# V1_0.net
KiCad netlist of a schematic drawn in Altium Designer
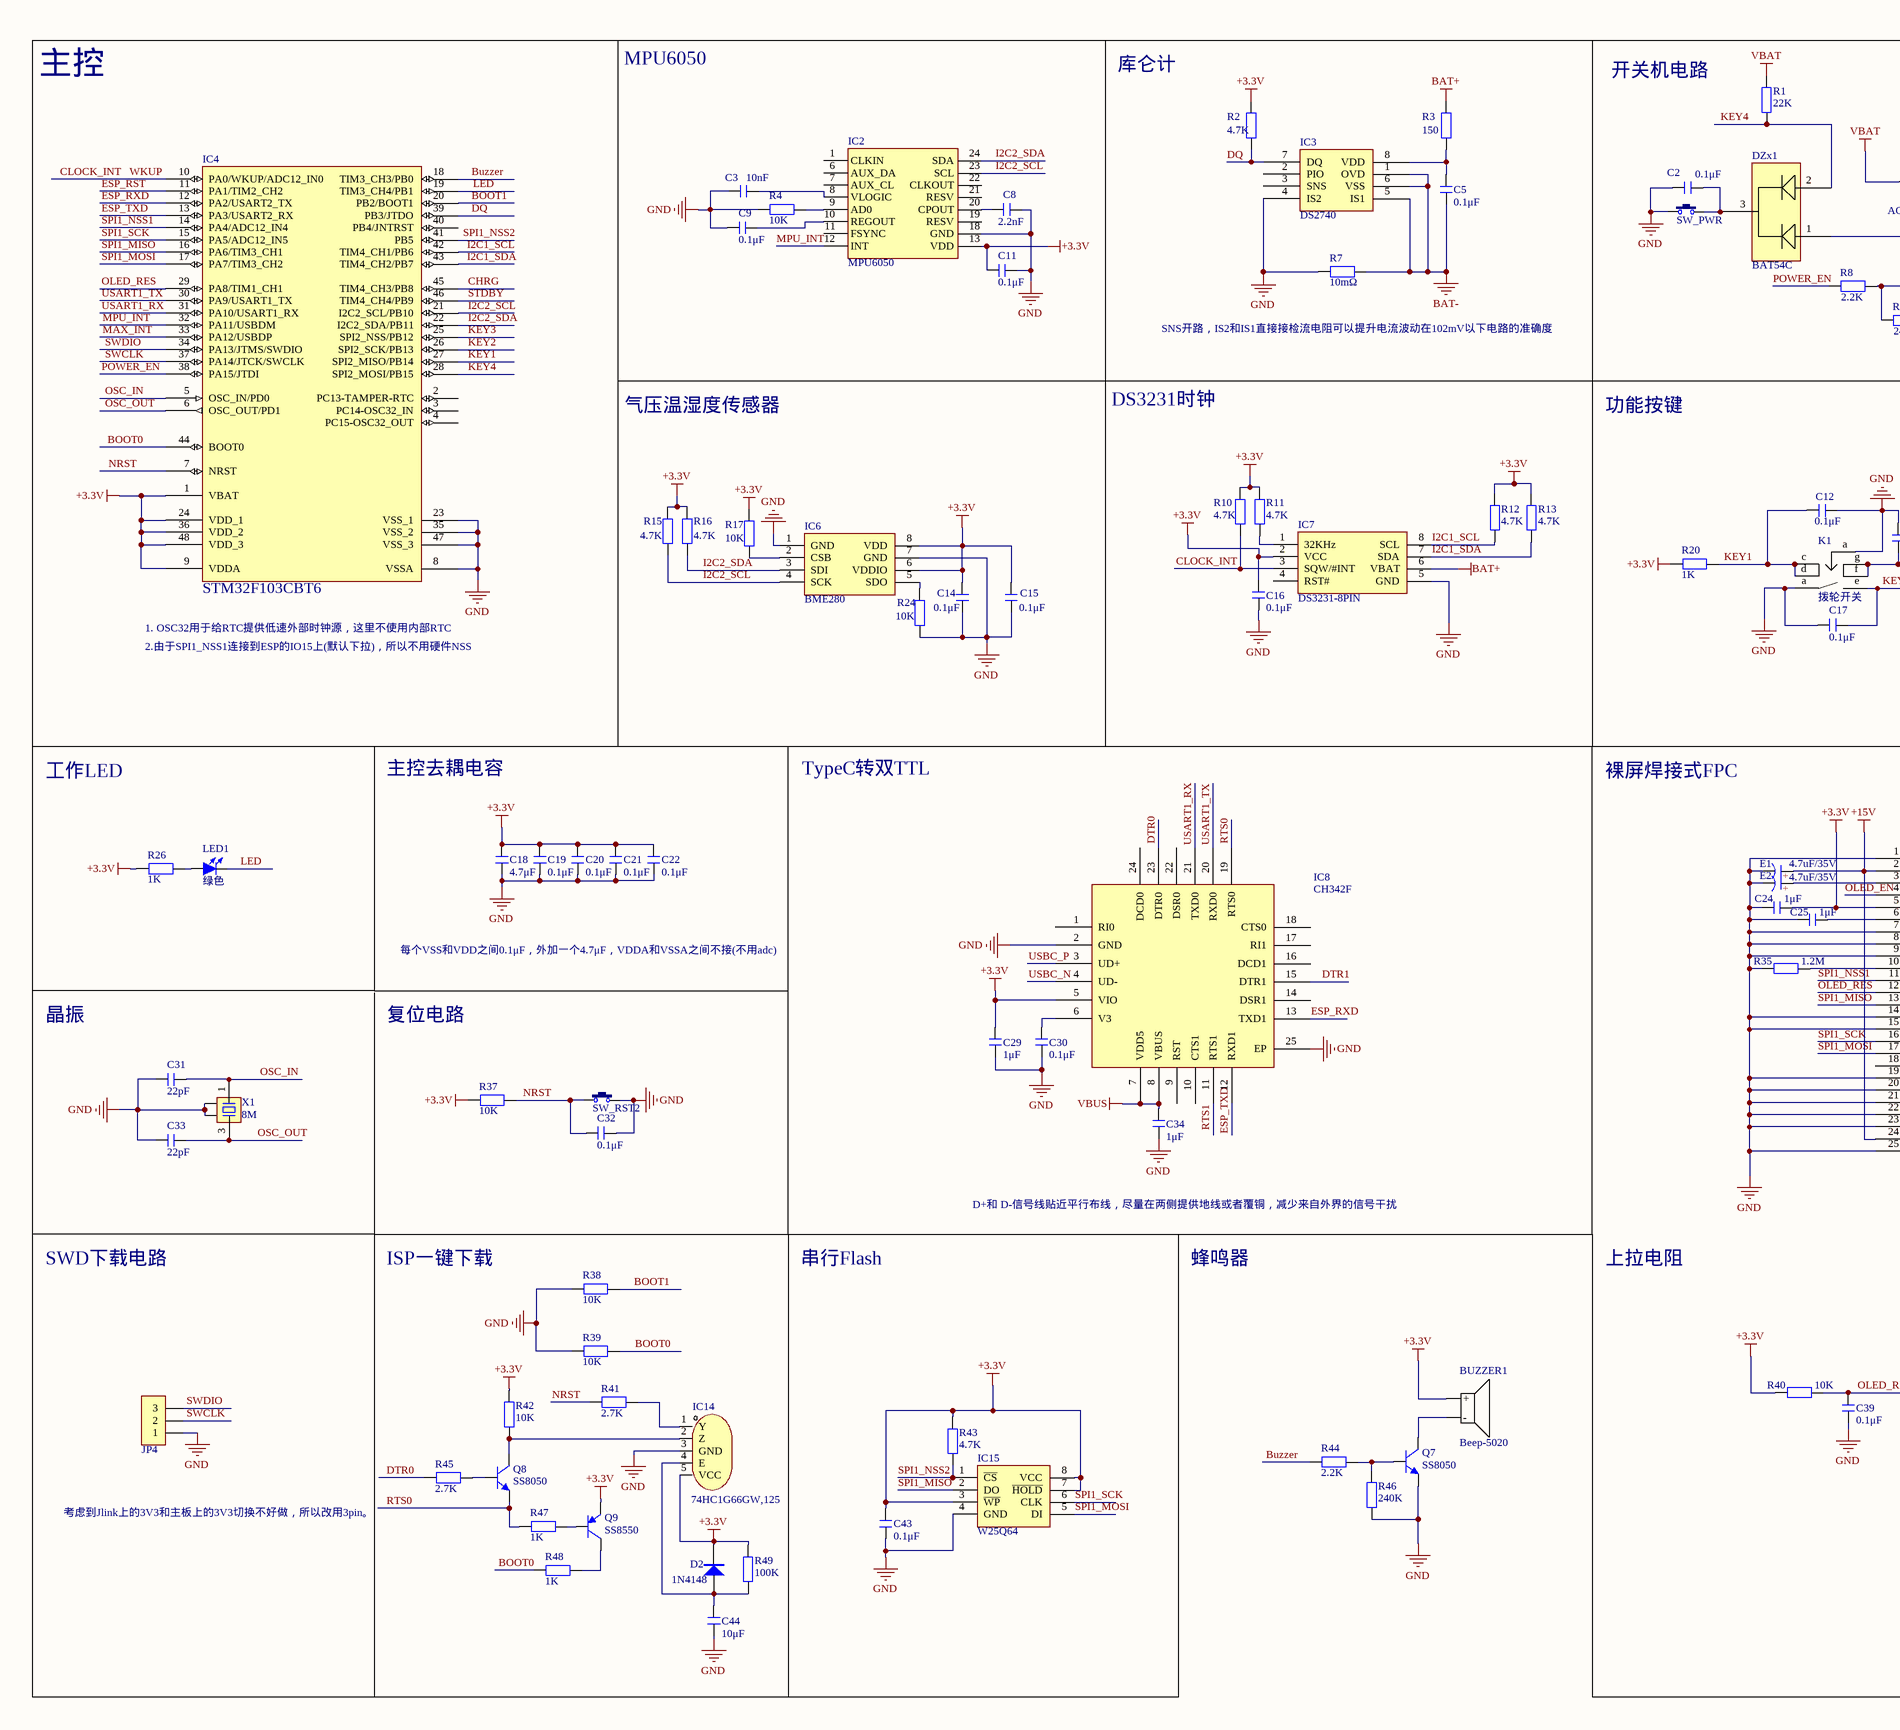
[diagram p0: V1.0.SchDoc, left]
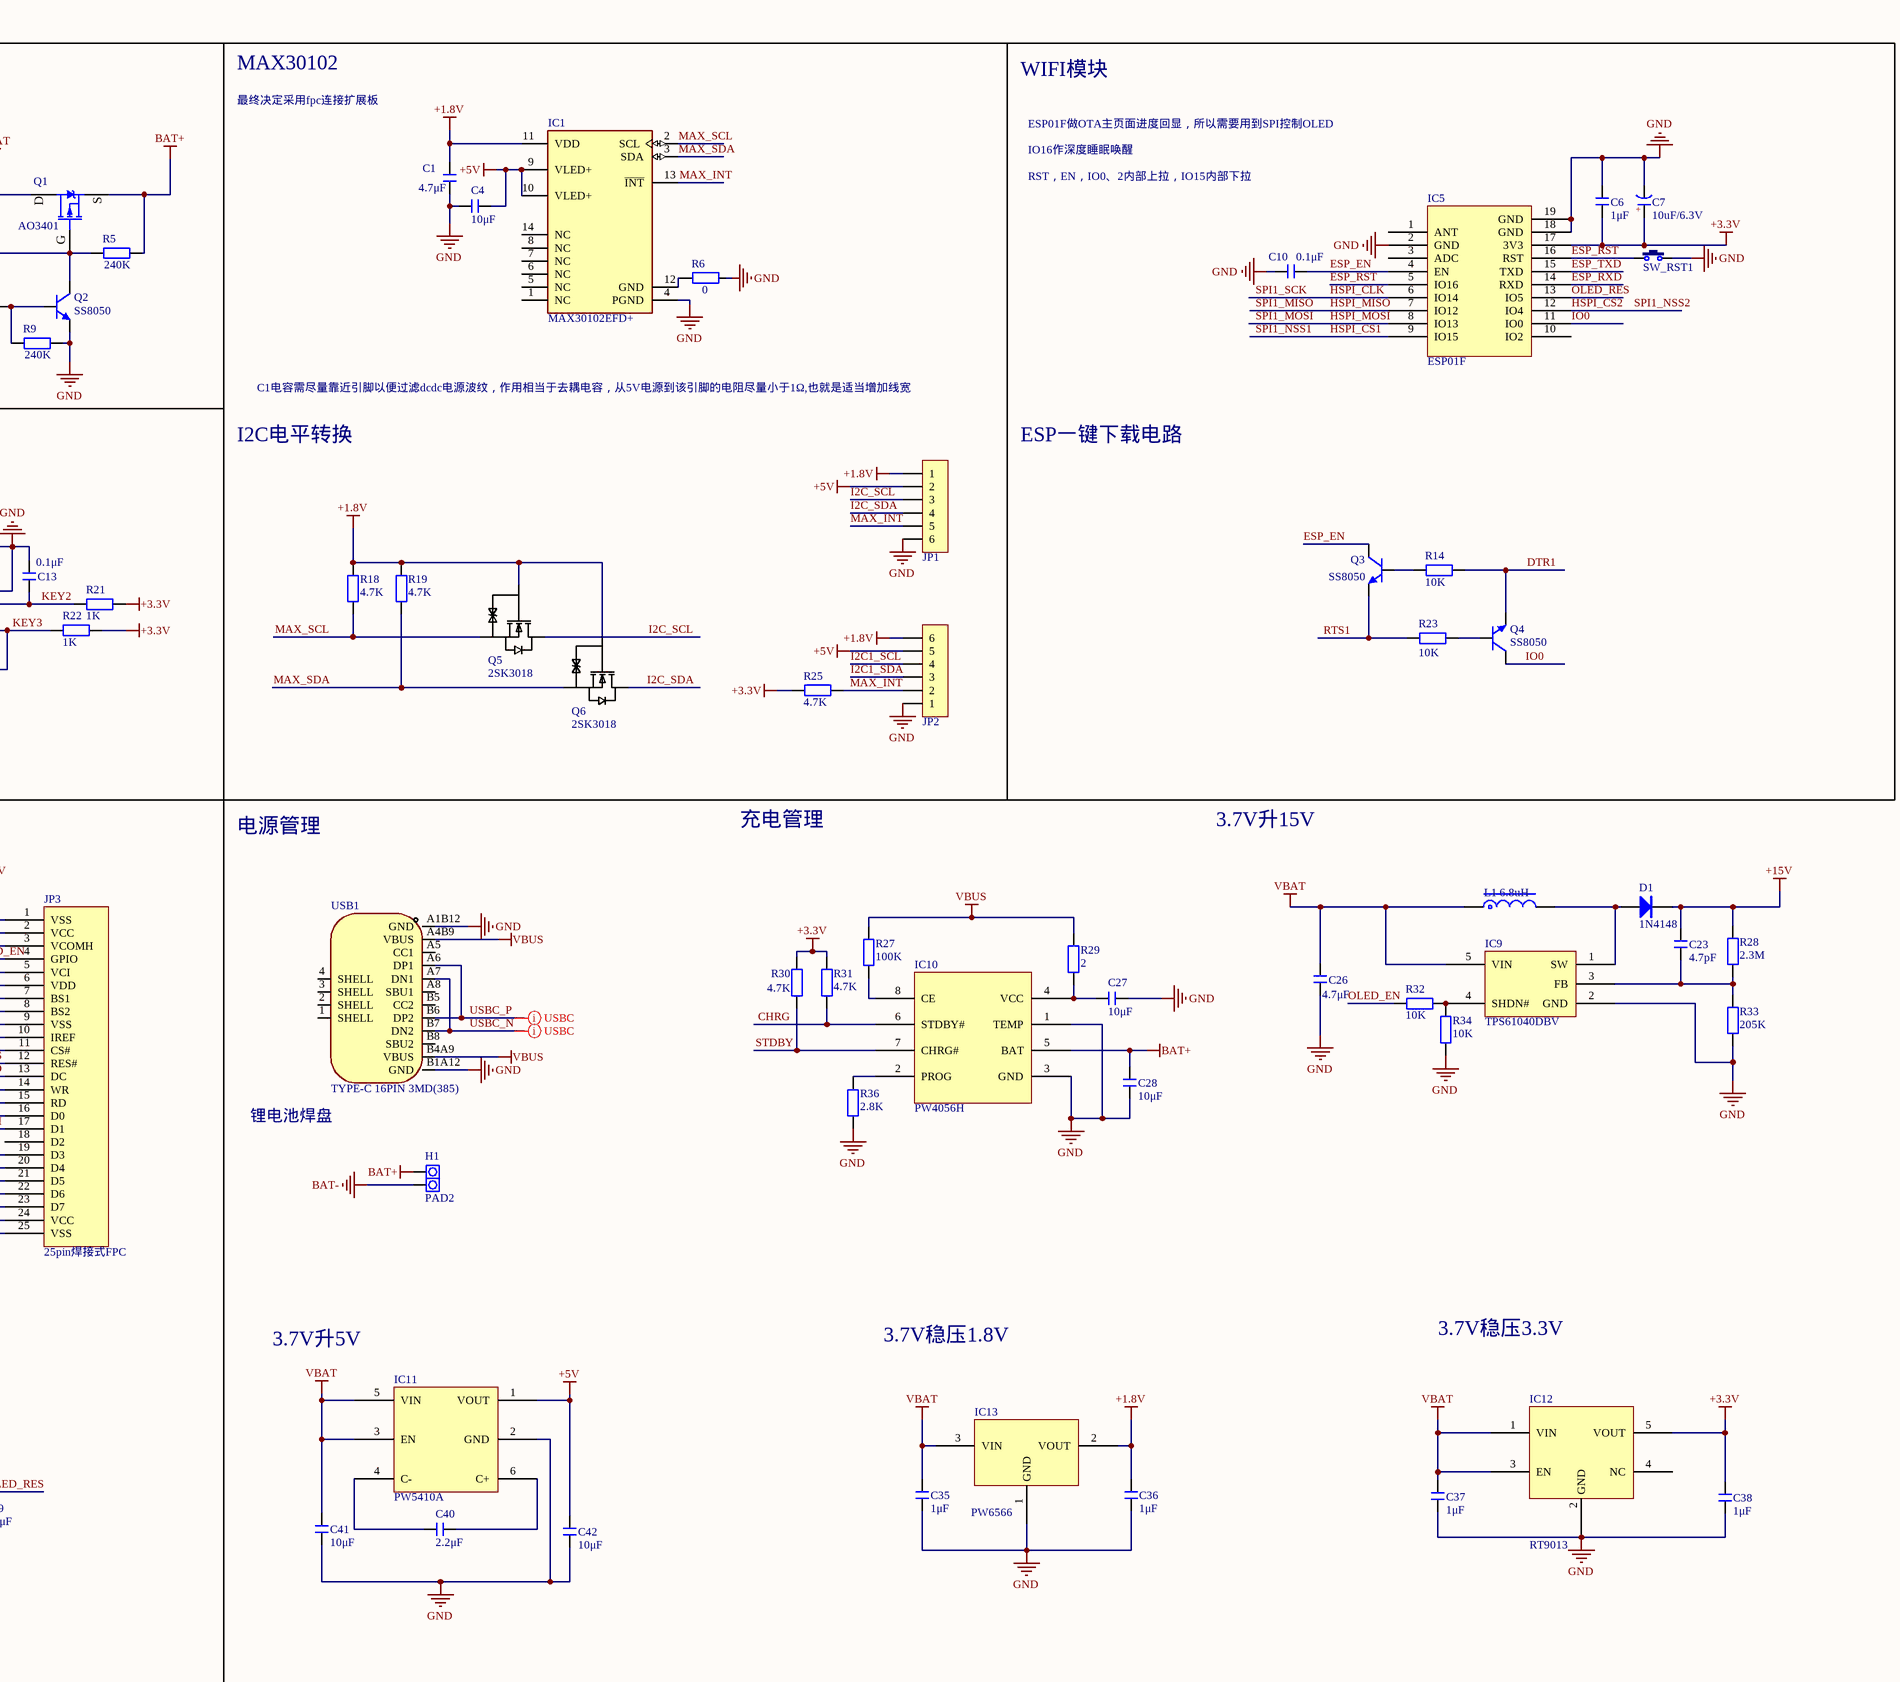
[diagram p1: V1.0.SchDoc, right]

(export (version "E")
  (design (tool "Eeschema 10.0.6"))
  (components
    (comp (ref "BUZZER1")
      (value "Beep-5020")
      (footprint "5020BUZZER")
      (description "贴片蜂鸣器5020最小封装")
      (libsource (lib "STM32_Watch") (part "Beep-5020"))
    )
    (comp (ref "C1")
      (value "4.7μF")
      (footprint "C 0603_L")
      (description "无极性贴片电容")
      (fields (field (name "版权归属") "源创客"))
      (libsource (lib "STM32_Watch") (part "C"))
    )
    (comp (ref "C2")
      (value "0.1μF")
      (footprint "C 0603_L")
      (description "无极性贴片电容")
      (fields (field (name "版权归属") "源创客"))
      (libsource (lib "STM32_Watch") (part "C"))
    )
    (comp (ref "C3")
      (value "10nF")
      (footprint "C 0603_L")
      (description "无极性贴片电容")
      (fields (field (name "版权归属") "源创客"))
      (libsource (lib "STM32_Watch") (part "C"))
    )
    (comp (ref "C4")
      (value "10μF")
      (footprint "C 0603_L")
      (description "无极性贴片电容")
      (fields (field (name "版权归属") "源创客"))
      (libsource (lib "STM32_Watch") (part "C"))
    )
    (comp (ref "C5")
      (value "0.1μF")
      (footprint "C 0603_L")
      (description "无极性贴片电容")
      (fields (field (name "版权归属") "源创客"))
      (libsource (lib "STM32_Watch") (part "C"))
    )
    (comp (ref "C6")
      (value "1μF")
      (footprint "C 0603_L")
      (description "无极性贴片电容")
      (fields (field (name "版权归属") "源创客"))
      (libsource (lib "STM32_Watch") (part "C"))
    )
    (comp (ref "C7")
      (value "10uF/6.3V")
      (footprint "CD A(3216)")
      (description "贴片钽电容")
      (fields (field (name "版权归属") "源创客"))
      (libsource (lib "STM32_Watch") (part "C-CD"))
    )
    (comp (ref "C8")
      (value "2.2nF")
      (footprint "C 0603_L")
      (description "无极性贴片电容")
      (fields (field (name "版权归属") "源创客"))
      (libsource (lib "STM32_Watch") (part "C"))
    )
    (comp (ref "C9")
      (value "0.1μF")
      (footprint "C 0603_L")
      (description "无极性贴片电容")
      (fields (field (name "版权归属") "源创客"))
      (libsource (lib "STM32_Watch") (part "C"))
    )
    (comp (ref "C10")
      (value "0.1μF")
      (footprint "C 0603_L")
      (description "无极性贴片电容")
      (fields (field (name "版权归属") "源创客"))
      (libsource (lib "STM32_Watch") (part "C"))
    )
    (comp (ref "C11")
      (value "0.1μF")
      (footprint "C 0603_L")
      (description "无极性贴片电容")
      (fields (field (name "版权归属") "源创客"))
      (libsource (lib "STM32_Watch") (part "C"))
    )
    (comp (ref "C12")
      (value "0.1μF")
      (footprint "C 0603_L")
      (description "无极性贴片电容")
      (fields (field (name "版权归属") "源创客"))
      (libsource (lib "STM32_Watch") (part "C"))
    )
    (comp (ref "C13")
      (value "0.1μF")
      (footprint "C 0603_L")
      (description "无极性贴片电容")
      (fields (field (name "版权归属") "源创客"))
      (libsource (lib "STM32_Watch") (part "C"))
    )
    (comp (ref "C14")
      (value "0.1μF")
      (footprint "C 0603_L")
      (description "无极性贴片电容")
      (fields (field (name "版权归属") "源创客"))
      (libsource (lib "STM32_Watch") (part "C"))
    )
    (comp (ref "C15")
      (value "0.1μF")
      (footprint "C 0603_L")
      (description "无极性贴片电容")
      (fields (field (name "版权归属") "源创客"))
      (libsource (lib "STM32_Watch") (part "C"))
    )
    (comp (ref "C16")
      (value "0.1μF")
      (footprint "C 0603_L")
      (description "无极性贴片电容")
      (fields (field (name "版权归属") "源创客"))
      (libsource (lib "STM32_Watch") (part "C"))
    )
    (comp (ref "C17")
      (value "0.1μF")
      (footprint "C 0603_L")
      (description "无极性贴片电容")
      (fields (field (name "版权归属") "源创客"))
      (libsource (lib "STM32_Watch") (part "C"))
    )
    (comp (ref "C18")
      (value "4.7μF")
      (footprint "C 0603_L")
      (description "无极性贴片电容")
      (fields (field (name "版权归属") "源创客"))
      (libsource (lib "STM32_Watch") (part "C"))
    )
    (comp (ref "C19")
      (value "0.1μF")
      (footprint "C 0603_L")
      (description "无极性贴片电容")
      (fields (field (name "版权归属") "源创客"))
      (libsource (lib "STM32_Watch") (part "C"))
    )
    (comp (ref "C20")
      (value "0.1μF")
      (footprint "C 0603_L")
      (description "无极性贴片电容")
      (fields (field (name "版权归属") "源创客"))
      (libsource (lib "STM32_Watch") (part "C"))
    )
    (comp (ref "C21")
      (value "0.1μF")
      (footprint "C 0603_L")
      (description "无极性贴片电容")
      (fields (field (name "版权归属") "源创客"))
      (libsource (lib "STM32_Watch") (part "C"))
    )
    (comp (ref "C22")
      (value "0.1μF")
      (footprint "C 0603_L")
      (description "无极性贴片电容")
      (fields (field (name "版权归属") "源创客"))
      (libsource (lib "STM32_Watch") (part "C"))
    )
    (comp (ref "C23")
      (value "4.7pF")
      (footprint "C 0603_L")
      (description "无极性贴片电容")
      (fields (field (name "版权归属") "源创客"))
      (libsource (lib "STM32_Watch") (part "C"))
    )
    (comp (ref "C24")
      (value "1μF")
      (footprint "C 0603_L")
      (description "无极性贴片电容")
      (fields (field (name "版权归属") "源创客"))
      (libsource (lib "STM32_Watch") (part "C"))
    )
    (comp (ref "C25")
      (value "1μF")
      (footprint "C 0603_L")
      (description "无极性贴片电容")
      (fields (field (name "版权归属") "源创客"))
      (libsource (lib "STM32_Watch") (part "C"))
    )
    (comp (ref "C26")
      (value "4.7μF")
      (footprint "C 0603_L")
      (description "无极性贴片电容")
      (fields (field (name "版权归属") "源创客"))
      (libsource (lib "STM32_Watch") (part "C"))
    )
    (comp (ref "C27")
      (value "10μF")
      (footprint "C 0603_L")
      (description "无极性贴片电容")
      (fields (field (name "版权归属") "源创客"))
      (libsource (lib "STM32_Watch") (part "C"))
    )
    (comp (ref "C28")
      (value "10μF")
      (footprint "C 0603_L")
      (description "无极性贴片电容")
      (fields (field (name "版权归属") "源创客"))
      (libsource (lib "STM32_Watch") (part "C"))
    )
    (comp (ref "C29")
      (value "1μF")
      (footprint "C 0603_L")
      (description "无极性贴片电容")
      (fields (field (name "版权归属") "源创客"))
      (libsource (lib "STM32_Watch") (part "C"))
    )
    (comp (ref "C30")
      (value "0.1μF")
      (footprint "C 0603_L")
      (description "无极性贴片电容")
      (fields (field (name "版权归属") "源创客"))
      (libsource (lib "STM32_Watch") (part "C"))
    )
    (comp (ref "C31")
      (value "22pF")
      (footprint "C 0603_L")
      (description "无极性贴片电容")
      (fields (field (name "版权归属") "源创客"))
      (libsource (lib "STM32_Watch") (part "C"))
    )
    (comp (ref "C32")
      (value "0.1μF")
      (footprint "C 0603_L")
      (description "无极性贴片电容")
      (fields (field (name "版权归属") "源创客"))
      (libsource (lib "STM32_Watch") (part "C"))
    )
    (comp (ref "C33")
      (value "22pF")
      (footprint "C 0603_L")
      (description "无极性贴片电容")
      (fields (field (name "版权归属") "源创客"))
      (libsource (lib "STM32_Watch") (part "C"))
    )
    (comp (ref "C34")
      (value "1μF")
      (footprint "C 0603_L")
      (description "无极性贴片电容")
      (fields (field (name "版权归属") "源创客"))
      (libsource (lib "STM32_Watch") (part "C"))
    )
    (comp (ref "C35")
      (value "1μF")
      (footprint "C 0603_L")
      (description "无极性贴片电容")
      (fields (field (name "版权归属") "源创客"))
      (libsource (lib "STM32_Watch") (part "C"))
    )
    (comp (ref "C36")
      (value "1μF")
      (footprint "C 0603_L")
      (description "无极性贴片电容")
      (fields (field (name "版权归属") "源创客"))
      (libsource (lib "STM32_Watch") (part "C"))
    )
    (comp (ref "C37")
      (value "1μF")
      (footprint "C 0603_L")
      (description "无极性贴片电容")
      (fields (field (name "版权归属") "源创客"))
      (libsource (lib "STM32_Watch") (part "C"))
    )
    (comp (ref "C38")
      (value "1μF")
      (footprint "C 0603_L")
      (description "无极性贴片电容")
      (fields (field (name "版权归属") "源创客"))
      (libsource (lib "STM32_Watch") (part "C"))
    )
    (comp (ref "C39")
      (value "0.1μF")
      (footprint "C 0603_L")
      (description "无极性贴片电容")
      (fields (field (name "版权归属") "源创客"))
      (libsource (lib "STM32_Watch") (part "C"))
    )
    (comp (ref "C40")
      (value "2.2μF")
      (footprint "C 0603_L")
      (description "无极性贴片电容")
      (fields (field (name "版权归属") "源创客"))
      (libsource (lib "STM32_Watch") (part "C"))
    )
    (comp (ref "C41")
      (value "10μF")
      (footprint "C 0603_L")
      (description "无极性贴片电容")
      (fields (field (name "版权归属") "源创客"))
      (libsource (lib "STM32_Watch") (part "C"))
    )
    (comp (ref "C42")
      (value "10μF")
      (footprint "C 0603_L")
      (description "无极性贴片电容")
      (fields (field (name "版权归属") "源创客"))
      (libsource (lib "STM32_Watch") (part "C"))
    )
    (comp (ref "C43")
      (value "0.1μF")
      (footprint "C 0603_L")
      (description "无极性贴片电容")
      (fields (field (name "版权归属") "源创客"))
      (libsource (lib "STM32_Watch") (part "C"))
    )
    (comp (ref "C44")
      (value "10μF")
      (footprint "C 0603_L")
      (description "无极性贴片电容")
      (fields (field (name "版权归属") "源创客"))
      (libsource (lib "STM32_Watch") (part "C"))
    )
    (comp (ref "D1")
      (value "1N4148")
      (footprint "SOD-123")
      (description "高速开关二极管")
      (fields (field (name "版权归属") "源创客"))
      (libsource (lib "STM32_Watch") (part "1N4148"))
    )
    (comp (ref "D2")
      (value "1N4148")
      (footprint "SOD-323")
      (description "高速开关二极管")
      (fields (field (name "版权归属") "源创客"))
      (libsource (lib "STM32_Watch") (part "1N4148"))
    )
    (comp (ref "DZx1")
      (value "BAT54C")
      (footprint "SOT23-3N")
      (description "双肖特基，共阴极")
      (libsource (lib "STM32_Watch") (part "BAT54C"))
    )
    (comp (ref "E1")
      (value "4.7uF/35V")
      (footprint "CD A(3216)")
      (description "贴片钽电容")
      (fields (field (name "版权归属") "源创客"))
      (libsource (lib "3.1   - 电阻-电容-电感") (part "C-CD"))
    )
    (comp (ref "E2")
      (value "4.7uF/35V")
      (footprint "CD A(3216)")
      (description "贴片钽电容")
      (fields (field (name "版权归属") "源创客"))
      (libsource (lib "3.1   - 电阻-电容-电感") (part "C-CD"))
    )
    (comp (ref "H1")
      (value "PAD2")
      (footprint "CHARGE_PAD")
      (description "引线焊盘")
      (fields (field (name "版权归属") "源创客"))
      (libsource (lib "STM32_Watch") (part "PAD2"))
    )
    (comp (ref "IC1")
      (value "MAX30102EFD+")
      (footprint "FP-F143A5-1-MFG")
      (description "IC SENSOR OXIMETER/HEARTRATE")
      (fields
        (field (name "MANUFACTURER") "Maxim Integrated")
        (field (name "OCTOPART") "https://octopart.com/max30102efd%2B-maxim+integrated-59568799")
      )
      (libsource (lib "STM32_Watch") (part "MAX30102"))
    )
    (comp (ref "IC2")
      (value "MPU6050")
      (footprint "QFN24 4x4_M")
      (description "陀螺仪")
      (libsource (lib "STM32_Watch") (part "MPU6050"))
    )
    (comp (ref "IC3")
      (value "DS2740")
      (footprint "MSOP8_L")
      (description "高精度库仑计")
      (libsource (lib "STM32_Watch") (part "DS2740"))
    )
    (comp (ref "IC4")
      (value "STM32F103CBT6")
      (footprint "LQFP48 7X7_M")
      (description "Flash:128/RAM:20/IO:48")
      (fields (field (name "版权归属") "源创客"))
      (libsource (lib "STM32_Watch") (part "STM32F103CB"))
    )
    (comp (ref "IC5") (value "ESP01F") (footprint "ESP-01F") (libsource (lib "STM32_Watch") (part "ESP01F")))
    (comp (ref "IC6")
      (value "BME280")
      (footprint "BME280")
      (description "气压，湿度，温度传感器")
      (libsource (lib "STM32_Watch") (part "BME280"))
    )
    (comp (ref "IC7")
      (value "DS3231-8PIN")
      (footprint "SOP8_N")
      (libsource (lib "STM32_Watch") (part "DS3231-8PIN"))
    )
    (comp (ref "IC8")
      (value "CH342F")
      (footprint "QFN24")
      (description "类型:-;协议类别:-;驱动器/接收器数:-;数据速率:-;")
      (fields (field (name "MANUFACTURER") "WCH(南京沁恒)"))
      (libsource (lib "STM32_Watch") (part "CH342F"))
    )
    (comp (ref "IC9")
      (value "TPS61040DBV")
      (footprint "SOT23-5L")
      (description "28V、400mA 开关升压转换器，适用于 LCD 和白光 LED")
      (libsource (lib "STM32_Watch") (part "TPS61040DBV"))
    )
    (comp (ref "IC10")
      (value "PW4056H")
      (footprint "SOP-8_L4.9-W3.9-P1.27-LS6.0-BL-EP3.1")
      (description "PW4056H 是一款完整的采用恒定电流/恒定电压的高压、大电流、单节鲤离子电池线性充电IC，最高耐压可达 28V，6.5V 自动过压保护，充电电流可达 1A。")
      (libsource (lib "STM32_Watch") (part "PW4056H"))
    )
    (comp (ref "IC11")
      (value "PW5410A")
      (footprint "SOT23-6")
      (description "低噪声，恒频 1.2MHZ，输入电压范围2.7v-5v，5v固定输出电压，输出电流250mA的DCDC升压")
      (libsource (lib "STM32_Watch") (part "PW5410A"))
    )
    (comp (ref "IC12")
      (value "RT9013")
      (footprint "SOT23-5L")
      (libsource (lib "STM32_Watch") (part "RT9013"))
    )
    (comp (ref "IC13")
      (value "PW6566")
      (footprint "SOT23-3L")
      (description "PW6566 系列是使用 CMOS 技术开发的低压差，高精度 输出电压，低消耗电流正电压型电压稳压器")
      (libsource (lib "STM32_Watch") (part "PW6566"))
    )
    (comp (ref "IC14")
      (value "74HC1G66GW,125")
      (footprint "SOT-353_L2.2-W1.4-P0.65-LS2.4-BR")
      (description "逻辑类型:SPST-NO;额外特性:-;")
      (fields (field (name "MANUFACTURER") "Nexperia(安世)"))
      (libsource (lib "STM32_Watch") (part "74HC1G66GW,125"))
    )
    (comp (ref "IC15")
      (value "W25Q64")
      (footprint "SOP8W_N")
      (description "外置Flash")
      (fields (field (name "版权归属") "源创客"))
      (libsource (lib "1.1   - IC芯片") (part "W25Qxx"))
    )
    (comp (ref "JP1")
      (value "FPC1.0-6P")
      (footprint "FPC0.5 2H-WS-6P")
      (description "FPC连接器")
      (fields (field (name "版权归属") "源创客"))
      (libsource (lib "") (part "FPC-6P_1"))
    )
    (comp (ref "JP2")
      (value "FPC1.0-6P")
      (footprint "FPC0.5 2H-WS-6P")
      (description "FPC连接器")
      (fields (field (name "版权归属") "源创客"))
      (libsource (lib "STM32_Watch") (part "FPC-6P"))
    )
    (comp (ref "JP3")
      (value "25pin焊接式FPC")
      (footprint "25pin焊接式FPC")
      (libsource (lib "STM32_Watch") (part "25pin焊接式FPC"))
    )
    (comp (ref "JP4")
      (value "HDR-1X3")
      (footprint "HDR2.54-3P")
      (description "3P接插件")
      (fields (field (name "版权归属") "源创客"))
      (libsource (lib "STM32_Watch") (part "Header 3"))
    )
    (comp (ref "K1") (value "拨轮开关") (footprint "拨轮开关") (libsource (lib "STM32_Watch") (part "拨轮开关")))
    (comp (ref "L1")
      (value "6.8uH")
      (footprint "NR3015")
      (description "NR磁胶电感")
      (fields (field (name "版权归属") "源创客"))
      (libsource (lib "STM32_Watch") (part "L-NR"))
    )
    (comp (ref "LED1")
      (value "绿色")
      (footprint "LED 0603G")
      (description "贴片LED")
      (fields (field (name "版权归属") "源创客"))
      (libsource (lib "STM32_Watch") (part "LED-SMD"))
    )
    (comp (ref "Q1")
      (value "AO3401")
      (footprint "SOT23-3N")
      (description "P沟道场效应管")
      (fields (field (name "版权归属") "源创客"))
      (libsource (lib "STM32_Watch") (part "AO3401"))
    )
    (comp (ref "Q2")
      (value "SS8050")
      (footprint "SOT23-3N")
      (description "高频放大-NPN型")
      (fields (field (name "版权归属") "源创客"))
      (libsource (lib "STM32_Watch") (part "8050-SMD"))
    )
    (comp (ref "Q3")
      (value "SS8050")
      (footprint "SOT23-3N")
      (description "高频放大-NPN型")
      (fields (field (name "版权归属") "源创客"))
      (libsource (lib "STM32_Watch") (part "8050-SMD"))
    )
    (comp (ref "Q4")
      (value "SS8050")
      (footprint "SOT23-3N")
      (description "高频放大-NPN型")
      (fields (field (name "版权归属") "源创客"))
      (libsource (lib "STM32_Watch") (part "8050-SMD"))
    )
    (comp (ref "Q5")
      (value "2SK3018")
      (footprint "SOT23-3L")
      (fields (field (name "MANUFACTURER") "TWGMC(台湾迪嘉)"))
      (libsource (lib "STM32_Watch") (part "2SK3018"))
    )
    (comp (ref "Q6")
      (value "2SK3018")
      (footprint "SOT23-3L")
      (fields (field (name "MANUFACTURER") "TWGMC(台湾迪嘉)"))
      (libsource (lib "STM32_Watch") (part "2SK3018"))
    )
    (comp (ref "Q7")
      (value "SS8050")
      (footprint "SOT23-3N")
      (description "高频放大-NPN型")
      (fields (field (name "版权归属") "源创客"))
      (libsource (lib "STM32_Watch") (part "8050-SMD"))
    )
    (comp (ref "Q8")
      (value "SS8050")
      (footprint "SOT23-3N")
      (description "高频放大-NPN型")
      (fields (field (name "版权归属") "源创客"))
      (libsource (lib "STM32_Watch") (part "8050-SMD"))
    )
    (comp (ref "Q9")
      (value "SS8550")
      (footprint "SOT23-3N")
      (description "高频放大-PNP型")
      (fields (field (name "版权归属") "源创客"))
      (libsource (lib "STM32_Watch") (part "8550-SMD"))
    )
    (comp (ref "R1")
      (value "22K")
      (footprint "R 0603_L")
      (description "贴片电阻")
      (fields (field (name "版权归属") "源创客"))
      (libsource (lib "STM32_Watch") (part "R"))
    )
    (comp (ref "R2")
      (value "4.7K")
      (footprint "R 0603_L")
      (description "贴片电阻")
      (fields (field (name "版权归属") "源创客"))
      (libsource (lib "STM32_Watch") (part "R"))
    )
    (comp (ref "R3")
      (value "150")
      (footprint "R 0603_L")
      (description "贴片电阻")
      (fields (field (name "版权归属") "源创客"))
      (libsource (lib "STM32_Watch") (part "R"))
    )
    (comp (ref "R4")
      (value "10K")
      (footprint "R 0603_L")
      (description "贴片电阻")
      (fields (field (name "版权归属") "源创客"))
      (libsource (lib "STM32_Watch") (part "R"))
    )
    (comp (ref "R5")
      (value "240K")
      (footprint "R 0603_L")
      (description "贴片电阻")
      (fields (field (name "版权归属") "源创客"))
      (libsource (lib "STM32_Watch") (part "R"))
    )
    (comp (ref "R6")
      (value "0")
      (footprint "R 0603_L")
      (description "贴片电阻")
      (fields (field (name "版权归属") "源创客"))
      (libsource (lib "STM32_Watch") (part "R"))
    )
    (comp (ref "R7")
      (value "10mΩ")
      (footprint "R 0603_L")
      (description "贴片电阻")
      (fields (field (name "版权归属") "源创客"))
      (libsource (lib "STM32_Watch") (part "R"))
    )
    (comp (ref "R8")
      (value "2.2K")
      (footprint "R 0603_L")
      (description "贴片电阻")
      (fields (field (name "版权归属") "源创客"))
      (libsource (lib "STM32_Watch") (part "R"))
    )
    (comp (ref "R9")
      (value "240K")
      (footprint "R 0603_L")
      (description "贴片电阻")
      (fields (field (name "版权归属") "源创客"))
      (libsource (lib "STM32_Watch") (part "R"))
    )
    (comp (ref "R10")
      (value "4.7K")
      (footprint "R 0603_L")
      (description "贴片电阻")
      (fields (field (name "版权归属") "源创客"))
      (libsource (lib "STM32_Watch") (part "R"))
    )
    (comp (ref "R11")
      (value "4.7K")
      (footprint "R 0603_L")
      (description "贴片电阻")
      (fields (field (name "版权归属") "源创客"))
      (libsource (lib "STM32_Watch") (part "R"))
    )
    (comp (ref "R12")
      (value "4.7K")
      (footprint "R 0603_L")
      (description "贴片电阻")
      (fields (field (name "版权归属") "源创客"))
      (libsource (lib "STM32_Watch") (part "R"))
    )
    (comp (ref "R13")
      (value "4.7K")
      (footprint "R 0603_L")
      (description "贴片电阻")
      (fields (field (name "版权归属") "源创客"))
      (libsource (lib "STM32_Watch") (part "R"))
    )
    (comp (ref "R14")
      (value "10K")
      (footprint "R 0603_L")
      (description "贴片电阻")
      (fields (field (name "版权归属") "源创客"))
      (libsource (lib "STM32_Watch") (part "R"))
    )
    (comp (ref "R15")
      (value "4.7K")
      (footprint "R 0603_L")
      (description "贴片电阻")
      (fields (field (name "版权归属") "源创客"))
      (libsource (lib "STM32_Watch") (part "R"))
    )
    (comp (ref "R16")
      (value "4.7K")
      (footprint "R 0603_L")
      (description "贴片电阻")
      (fields (field (name "版权归属") "源创客"))
      (libsource (lib "STM32_Watch") (part "R"))
    )
    (comp (ref "R17")
      (value "10K")
      (footprint "R 0603_L")
      (description "贴片电阻")
      (fields (field (name "版权归属") "源创客"))
      (libsource (lib "STM32_Watch") (part "R"))
    )
    (comp (ref "R18")
      (value "4.7K")
      (footprint "R 0603_L")
      (description "贴片电阻")
      (fields (field (name "版权归属") "源创客"))
      (libsource (lib "STM32_Watch") (part "R"))
    )
    (comp (ref "R19")
      (value "4.7K")
      (footprint "R 0603_L")
      (description "贴片电阻")
      (fields (field (name "版权归属") "源创客"))
      (libsource (lib "STM32_Watch") (part "R"))
    )
    (comp (ref "R20")
      (value "1K")
      (footprint "R 0603_L")
      (description "贴片电阻")
      (fields (field (name "版权归属") "源创客"))
      (libsource (lib "STM32_Watch") (part "R"))
    )
    (comp (ref "R21")
      (value "1K")
      (footprint "R 0603_L")
      (description "贴片电阻")
      (fields (field (name "版权归属") "源创客"))
      (libsource (lib "STM32_Watch") (part "R"))
    )
    (comp (ref "R22")
      (value "1K")
      (footprint "R 0603_L")
      (description "贴片电阻")
      (fields (field (name "版权归属") "源创客"))
      (libsource (lib "STM32_Watch") (part "R"))
    )
    (comp (ref "R23")
      (value "10K")
      (footprint "R 0603_L")
      (description "贴片电阻")
      (fields (field (name "版权归属") "源创客"))
      (libsource (lib "STM32_Watch") (part "R"))
    )
    (comp (ref "R24")
      (value "10K")
      (footprint "R 0603_L")
      (description "贴片电阻")
      (fields (field (name "版权归属") "源创客"))
      (libsource (lib "STM32_Watch") (part "R"))
    )
    (comp (ref "R25")
      (value "4.7K")
      (footprint "R 0603_L")
      (description "贴片电阻")
      (fields (field (name "版权归属") "源创客"))
      (libsource (lib "STM32_Watch") (part "R"))
    )
    (comp (ref "R26")
      (value "1K")
      (footprint "R 0603_L")
      (description "贴片电阻")
      (fields (field (name "版权归属") "源创客"))
      (libsource (lib "STM32_Watch") (part "R"))
    )
    (comp (ref "R27")
      (value "100K")
      (footprint "R 0603_L")
      (description "贴片电阻")
      (fields (field (name "版权归属") "源创客"))
      (libsource (lib "STM32_Watch") (part "R"))
    )
    (comp (ref "R28")
      (value "2.3M")
      (footprint "R 0603_L")
      (description "贴片电阻")
      (fields (field (name "版权归属") "源创客"))
      (libsource (lib "STM32_Watch") (part "R"))
    )
    (comp (ref "R29")
      (value "2")
      (footprint "R 0603_L")
      (description "贴片电阻")
      (fields (field (name "版权归属") "源创客"))
      (libsource (lib "STM32_Watch") (part "R"))
    )
    (comp (ref "R30")
      (value "4.7K")
      (footprint "R 0603_L")
      (description "贴片电阻")
      (fields (field (name "版权归属") "源创客"))
      (libsource (lib "STM32_Watch") (part "R"))
    )
    (comp (ref "R31")
      (value "4.7K")
      (footprint "R 0603_L")
      (description "贴片电阻")
      (fields (field (name "版权归属") "源创客"))
      (libsource (lib "STM32_Watch") (part "R"))
    )
    (comp (ref "R32")
      (value "10K")
      (footprint "R 0603_L")
      (description "贴片电阻")
      (fields (field (name "版权归属") "源创客"))
      (libsource (lib "STM32_Watch") (part "R"))
    )
    (comp (ref "R33")
      (value "205K")
      (footprint "R 0603_L")
      (description "贴片电阻")
      (fields (field (name "版权归属") "源创客"))
      (libsource (lib "STM32_Watch") (part "R"))
    )
    (comp (ref "R34")
      (value "10K")
      (footprint "R 0603_L")
      (description "贴片电阻")
      (fields (field (name "版权归属") "源创客"))
      (libsource (lib "STM32_Watch") (part "R"))
    )
    (comp (ref "R35")
      (value "1.2M")
      (footprint "R 0603_L")
      (description "贴片电阻")
      (fields (field (name "版权归属") "源创客"))
      (libsource (lib "STM32_Watch") (part "R"))
    )
    (comp (ref "R36")
      (value "2.8K")
      (footprint "R 0603_L")
      (description "贴片电阻")
      (fields (field (name "版权归属") "源创客"))
      (libsource (lib "STM32_Watch") (part "R"))
    )
    (comp (ref "R37")
      (value "10K")
      (footprint "R 0603_L")
      (description "贴片电阻")
      (fields (field (name "版权归属") "源创客"))
      (libsource (lib "STM32_Watch") (part "R"))
    )
    (comp (ref "R38")
      (value "10K")
      (footprint "R 0603_L")
      (description "贴片电阻")
      (fields (field (name "版权归属") "源创客"))
      (libsource (lib "STM32_Watch") (part "R"))
    )
    (comp (ref "R39")
      (value "10K")
      (footprint "R 0603_L")
      (description "贴片电阻")
      (fields (field (name "版权归属") "源创客"))
      (libsource (lib "STM32_Watch") (part "R"))
    )
    (comp (ref "R40")
      (value "10K")
      (footprint "R 0603_L")
      (description "贴片电阻")
      (fields (field (name "版权归属") "源创客"))
      (libsource (lib "STM32_Watch") (part "R"))
    )
    (comp (ref "R41")
      (value "2.7K")
      (footprint "R 0603_L")
      (description "贴片电阻")
      (fields (field (name "版权归属") "源创客"))
      (libsource (lib "STM32_Watch") (part "R"))
    )
    (comp (ref "R42")
      (value "10K")
      (footprint "R 0603_L")
      (description "贴片电阻")
      (fields (field (name "版权归属") "源创客"))
      (libsource (lib "STM32_Watch") (part "R"))
    )
    (comp (ref "R43")
      (value "4.7K")
      (footprint "R 0603_L")
      (description "贴片电阻")
      (fields (field (name "版权归属") "源创客"))
      (libsource (lib "STM32_Watch") (part "R"))
    )
    (comp (ref "R44")
      (value "2.2K")
      (footprint "R 0603_L")
      (description "贴片电阻")
      (fields (field (name "版权归属") "源创客"))
      (libsource (lib "STM32_Watch") (part "R"))
    )
    (comp (ref "R45")
      (value "2.7K")
      (footprint "R 0603_L")
      (description "贴片电阻")
      (fields (field (name "版权归属") "源创客"))
      (libsource (lib "STM32_Watch") (part "R"))
    )
    (comp (ref "R46")
      (value "240K")
      (footprint "R 0603_L")
      (description "贴片电阻")
      (fields (field (name "版权归属") "源创客"))
      (libsource (lib "STM32_Watch") (part "R"))
    )
    (comp (ref "R47")
      (value "1K")
      (footprint "R 0603_L")
      (description "贴片电阻")
      (fields (field (name "版权归属") "源创客"))
      (libsource (lib "STM32_Watch") (part "R"))
    )
    (comp (ref "R48")
      (value "1K")
      (footprint "R 0603_L")
      (description "贴片电阻")
      (fields (field (name "版权归属") "源创客"))
      (libsource (lib "STM32_Watch") (part "R"))
    )
    (comp (ref "R49")
      (value "100K")
      (footprint "R 0603_L")
      (description "贴片电阻")
      (fields (field (name "版权归属") "源创客"))
      (libsource (lib "STM32_Watch") (part "R"))
    )
    (comp (ref "SW_PWR")
      (value "3")
      (footprint "KEY-SMD_UK-B0264-SP25Y")
      (description "2x4x3.5轻触开关")
      (fields (field (name "版权归属") "源创客"))
      (libsource (lib "STM32_Watch") (part "TSW 2x4x3.5"))
    )
    (comp (ref "SW_RST1")
      (value "3x4x2")
      (footprint "SW-SMD_L4.0-W3.0-LS4.6")
      (description "3x4x2开关")
      (fields (field (name "版权归属") "源创客"))
      (libsource (lib "STM32_Watch") (part "TSW 3x4x2"))
    )
    (comp (ref "SW_RST2")
      (value "3x4x2")
      (footprint "SW-SMD_L4.0-W3.0-LS4.6")
      (description "3x4x2开关")
      (fields (field (name "版权归属") "源创客"))
      (libsource (lib "STM32_Watch") (part "TSW 3x4x2"))
    )
    (comp (ref "USB1")
      (value "TYPE-C 16PIN 3MD(385)")
      (footprint "USB-C-SMD_KH-TYPE-C-16P")
      (description "连接器类型:Type-C;标准:-;公母:母座;触点数量:16;端口数量:1;安装方式:卧贴;额定电流 - 电源:3A;工作温度范围:-40℃~+85℃;")
      (fields (field (name "MANUFACTURER") "SHOU HAN(首韩)"))
      (libsource (lib "STM32_Watch") (part "TYPE-C 16PIN 3MD(385)"))
    )
    (comp (ref "X1")
      (value "8M")
      (footprint "OSC 3225-4P")
      (description "4脚无源晶振")
      (fields (field (name "版权归属") "源创客"))
      (libsource (lib "STM32_Watch") (part "XTAL-4P"))
    )
  )
  (nets
    (net (code "1") (name "+1.8V") (class "Default")
      (node (ref "C1") (pin "1") (pinfunction "1_1") (pintype "passive"))
      (node (ref "C36") (pin "1") (pinfunction "1_1") (pintype "passive"))
      (node (ref "IC1") (pin "11") (pinfunction "VDD_11") (pintype "power_in"))
      (node (ref "IC13") (pin "2") (pinfunction "VOUT_2") (pintype "passive"))
      (node (ref "JP1") (pin "1") (pinfunction "1_1") (pintype "passive"))
      (node (ref "JP2") (pin "6") (pinfunction "6_6") (pintype "passive"))
      (node (ref "Q5") (pin "1") (pinfunction "G_1") (pintype "passive"))
      (node (ref "Q6") (pin "1") (pinfunction "G_1") (pintype "passive"))
      (node (ref "R18") (pin "1") (pinfunction "1_1") (pintype "passive"))
      (node (ref "R19") (pin "1") (pinfunction "1_1") (pintype "passive"))
    )
    (net (code "2") (name "+3.3V") (class "Default")
      (node (ref "BUZZER1") (pin "1") (pinfunction "+_1") (pintype "passive"))
      (node (ref "C11") (pin "2") (pinfunction "2_2") (pintype "passive"))
      (node (ref "C14") (pin "1") (pinfunction "1_1") (pintype "passive"))
      (node (ref "C15") (pin "1") (pinfunction "1_1") (pintype "passive"))
      (node (ref "C16") (pin "1") (pinfunction "1_1") (pintype "passive"))
      (node (ref "C18") (pin "2") (pinfunction "2_2") (pintype "passive"))
      (node (ref "C19") (pin "2") (pinfunction "2_2") (pintype "passive"))
      (node (ref "C20") (pin "2") (pinfunction "2_2") (pintype "passive"))
      (node (ref "C21") (pin "2") (pinfunction "2_2") (pintype "passive"))
      (node (ref "C22") (pin "2") (pinfunction "2_2") (pintype "passive"))
      (node (ref "C24") (pin "2") (pinfunction "2_2") (pintype "passive"))
      (node (ref "C29") (pin "1") (pinfunction "1_1") (pintype "passive"))
      (node (ref "C38") (pin "1") (pinfunction "1_1") (pintype "passive"))
      (node (ref "C43") (pin "2") (pinfunction "2_2") (pintype "passive"))
      (node (ref "C6") (pin "1") (pinfunction "1_1") (pintype "passive"))
      (node (ref "C7") (pin "1") (pinfunction "A_1") (pintype "passive"))
      (node (ref "D2") (pin "2") (pinfunction "K_2") (pintype "passive"))
      (node (ref "IC12") (pin "5") (pinfunction "VOUT_5") (pintype "passive"))
      (node (ref "IC14") (pin "5") (pinfunction "VCC_5") (pintype "passive"))
      (node (ref "IC15") (pin "3") (pinfunction "~{WP}_3") (pintype "passive"))
      (node (ref "IC15") (pin "7") (pinfunction "~{HOLD}_7") (pintype "passive"))
      (node (ref "IC15") (pin "8") (pinfunction "VCC_8") (pintype "passive"))
      (node (ref "IC2") (pin "13") (pinfunction "VDD_13") (pintype "passive"))
      (node (ref "IC4") (pin "1") (pinfunction "VBAT_1") (pintype "power_in"))
      (node (ref "IC4") (pin "24") (pinfunction "VDD_1_24") (pintype "power_in"))
      (node (ref "IC4") (pin "36") (pinfunction "VDD_2_36") (pintype "power_in"))
      (node (ref "IC4") (pin "48") (pinfunction "VDD_3_48") (pintype "power_in"))
      (node (ref "IC4") (pin "9") (pinfunction "VDDA_9") (pintype "power_in"))
      (node (ref "IC5") (pin "17") (pinfunction "3V3_17") (pintype "passive"))
      (node (ref "IC6") (pin "6") (pinfunction "VDDIO_6") (pintype "passive"))
      (node (ref "IC6") (pin "8") (pinfunction "VDD_8") (pintype "passive"))
      (node (ref "IC7") (pin "2") (pinfunction "VCC_2") (pintype "passive"))
      (node (ref "IC8") (pin "5") (pinfunction "VIO_5") (pintype "passive"))
      (node (ref "JP3") (pin "5") (pinfunction "VCI_5") (pintype "passive"))
      (node (ref "Q9") (pin "2") (pinfunction "E_2") (pintype "passive"))
      (node (ref "R10") (pin "1") (pinfunction "1_1") (pintype "passive"))
      (node (ref "R11") (pin "1") (pinfunction "1_1") (pintype "passive"))
      (node (ref "R12") (pin "1") (pinfunction "1_1") (pintype "passive"))
      (node (ref "R13") (pin "1") (pinfunction "1_1") (pintype "passive"))
      (node (ref "R15") (pin "1") (pinfunction "1_1") (pintype "passive"))
      (node (ref "R16") (pin "1") (pinfunction "1_1") (pintype "passive"))
      (node (ref "R17") (pin "2") (pinfunction "2_2") (pintype "passive"))
      (node (ref "R2") (pin "2") (pinfunction "2_2") (pintype "passive"))
      (node (ref "R20") (pin "2") (pinfunction "2_2") (pintype "passive"))
      (node (ref "R21") (pin "2") (pinfunction "2_2") (pintype "passive"))
      (node (ref "R22") (pin "2") (pinfunction "2_2") (pintype "passive"))
      (node (ref "R25") (pin "2") (pinfunction "2_2") (pintype "passive"))
      (node (ref "R26") (pin "2") (pinfunction "2_2") (pintype "passive"))
      (node (ref "R30") (pin "2") (pinfunction "2_2") (pintype "passive"))
      (node (ref "R31") (pin "2") (pinfunction "2_2") (pintype "passive"))
      (node (ref "R37") (pin "2") (pinfunction "2_2") (pintype "passive"))
      (node (ref "R40") (pin "1") (pinfunction "1_1") (pintype "passive"))
      (node (ref "R42") (pin "1") (pinfunction "1_1") (pintype "passive"))
      (node (ref "R43") (pin "2") (pinfunction "2_2") (pintype "passive"))
      (node (ref "R49") (pin "2") (pinfunction "2_2") (pintype "passive"))
    )
    (net (code "3") (name "+5V") (class "Default")
      (node (ref "C4") (pin "2") (pinfunction "2_2") (pintype "passive"))
      (node (ref "C42") (pin "1") (pinfunction "1_1") (pintype "passive"))
      (node (ref "IC1") (pin "10") (pinfunction "VLED+_10") (pintype "power_in"))
      (node (ref "IC1") (pin "9") (pinfunction "VLED+_9") (pintype "power_in"))
      (node (ref "IC11") (pin "1") (pinfunction "VOUT_1") (pintype "passive"))
      (node (ref "JP1") (pin "2") (pinfunction "2_2") (pintype "passive"))
      (node (ref "JP2") (pin "5") (pinfunction "5_5") (pintype "passive"))
    )
    (net (code "4") (name "+15V") (class "Default")
      (node (ref "C23") (pin "2") (pinfunction "2_2") (pintype "passive"))
      (node (ref "D1") (pin "2") (pinfunction "K_2") (pintype "passive"))
      (node (ref "E1") (pin "1") (pinfunction "A_1") (pintype "passive"))
      (node (ref "JP3") (pin "2") (pinfunction "VCC_2") (pintype "passive"))
      (node (ref "JP3") (pin "24") (pinfunction "VCC_24") (pintype "passive"))
      (node (ref "R28") (pin "2") (pinfunction "2_2") (pintype "passive"))
    )
    (net (code "5") (name "/BOOT0") (class "Default")
      (node (ref "IC4") (pin "44") (pinfunction "BOOT0_44") (pintype "bidirectional"))
      (node (ref "R39") (pin "1") (pinfunction "1_1") (pintype "passive"))
      (node (ref "R48") (pin "1") (pinfunction "1_1") (pintype "passive"))
    )
    (net (code "6") (name "/BOOT1") (class "Default")
      (node (ref "IC4") (pin "20") (pinfunction "PB2/BOOT1_20") (pintype "bidirectional"))
      (node (ref "R38") (pin "1") (pinfunction "1_1") (pintype "passive"))
    )
    (net (code "7") (name "/Buzzer") (class "Default")
      (node (ref "IC4") (pin "18") (pinfunction "TIM3_CH3/PB0_18") (pintype "bidirectional"))
      (node (ref "R44") (pin "1") (pinfunction "1_1") (pintype "passive"))
    )
    (net (code "8") (name "/CHRG") (class "Default")
      (node (ref "IC10") (pin "6") (pinfunction "STDBY#_6") (pintype "passive"))
      (node (ref "IC4") (pin "45") (pinfunction "TIM4_CH3/PB8_45") (pintype "bidirectional"))
      (node (ref "R31") (pin "1") (pinfunction "1_1") (pintype "passive"))
    )
    (net (code "9") (name "/CLOCK_INT") (class "Default")
      (node (ref "IC4") (pin "10") (pinfunction "PA0/WKUP/ADC12_IN0_10") (pintype "bidirectional"))
      (node (ref "IC7") (pin "3") (pinfunction "SQW/#INT_3") (pintype "passive"))
      (node (ref "R10") (pin "2") (pinfunction "2_2") (pintype "passive"))
    )
    (net (code "10") (name "/DQ") (class "Default")
      (node (ref "IC3") (pin "7") (pinfunction "DQ_7") (pintype "passive"))
      (node (ref "IC4") (pin "39") (pinfunction "PB3/JTDO_39") (pintype "bidirectional"))
      (node (ref "R2") (pin "1") (pinfunction "1_1") (pintype "passive"))
    )
    (net (code "11") (name "/DTR0") (class "Default")
      (node (ref "IC8") (pin "23") (pinfunction "DTR0_23") (pintype "passive"))
      (node (ref "R45") (pin "1") (pinfunction "1_1") (pintype "passive"))
    )
    (net (code "12") (name "/DTR1") (class "Default")
      (node (ref "IC8") (pin "15") (pinfunction "DTR1_15") (pintype "passive"))
      (node (ref "Q4") (pin "2") (pinfunction "E_2") (pintype "passive"))
      (node (ref "R14") (pin "1") (pinfunction "1_1") (pintype "passive"))
    )
    (net (code "13") (name "/ESP_EN") (class "Default")
      (node (ref "C10") (pin "2") (pinfunction "2_2") (pintype "passive"))
      (node (ref "IC5") (pin "4") (pinfunction "EN_4") (pintype "passive"))
      (node (ref "Q3") (pin "3") (pinfunction "C_3") (pintype "passive"))
    )
    (net (code "14") (name "/ESP_RST") (class "Default")
      (node (ref "IC4") (pin "11") (pinfunction "PA1/TIM2_CH2_11") (pintype "bidirectional"))
      (node (ref "IC5") (pin "16") (pinfunction "RST_16") (pintype "passive"))
      (node (ref "IC5") (pin "5") (pinfunction "IO16_5") (pintype "passive"))
      (node (ref "SW_RST1") (pin "1") (pinfunction "1_1") (pintype "passive"))
    )
    (net (code "15") (name "/ESP_RXD") (class "Default")
      (node (ref "IC4") (pin "12") (pinfunction "PA2/USART2_TX_12") (pintype "bidirectional"))
      (node (ref "IC5") (pin "14") (pinfunction "RXD_14") (pintype "passive"))
      (node (ref "IC8") (pin "13") (pinfunction "TXD1_13") (pintype "passive"))
    )
    (net (code "16") (name "/ESP_TXD") (class "Default")
      (node (ref "IC4") (pin "13") (pinfunction "PA3/USART2_RX_13") (pintype "bidirectional"))
      (node (ref "IC5") (pin "15") (pinfunction "TXD_15") (pintype "passive"))
      (node (ref "IC8") (pin "12") (pinfunction "RXD1_12") (pintype "passive"))
    )
    (net (code "17") (name "/HSPI_CLK") (class "Default")
      (node (ref "IC15") (pin "6") (pinfunction "CLK_6") (pintype "passive"))
      (node (ref "IC4") (pin "15") (pinfunction "PA5/ADC12_IN5_15") (pintype "bidirectional"))
      (node (ref "IC5") (pin "6") (pinfunction "IO14_6") (pintype "passive"))
      (node (ref "JP3") (pin "16") (pinfunction "D0_16") (pintype "passive"))
    )
    (net (code "18") (name "/HSPI_CS1") (class "Default")
      (node (ref "IC4") (pin "14") (pinfunction "PA4/ADC12_IN4_14") (pintype "bidirectional"))
      (node (ref "IC5") (pin "9") (pinfunction "IO15_9") (pintype "passive"))
      (node (ref "JP3") (pin "11") (pinfunction "CS#_11") (pintype "passive"))
    )
    (net (code "19") (name "/HSPI_CS2") (class "Default")
      (node (ref "IC15") (pin "1") (pinfunction "~{CS}_1") (pintype "passive"))
      (node (ref "IC4") (pin "41") (pinfunction "PB5_41") (pintype "bidirectional"))
      (node (ref "IC5") (pin "12") (pinfunction "IO4_12") (pintype "passive"))
      (node (ref "R43") (pin "1") (pinfunction "1_1") (pintype "passive"))
    )
    (net (code "20") (name "/HSPI_MISO") (class "Default")
      (node (ref "IC15") (pin "2") (pinfunction "DO_2") (pintype "passive"))
      (node (ref "IC4") (pin "16") (pinfunction "PA6/TIM3_CH1_16") (pintype "bidirectional"))
      (node (ref "IC5") (pin "7") (pinfunction "IO12_7") (pintype "passive"))
      (node (ref "JP3") (pin "13") (pinfunction "DC_13") (pintype "passive"))
    )
    (net (code "21") (name "/HSPI_MOSI") (class "Default")
      (node (ref "IC15") (pin "5") (pinfunction "DI_5") (pintype "passive"))
      (node (ref "IC4") (pin "17") (pinfunction "PA7/TIM3_CH2_17") (pintype "bidirectional"))
      (node (ref "IC5") (pin "8") (pinfunction "IO13_8") (pintype "passive"))
      (node (ref "JP3") (pin "17") (pinfunction "D1_17") (pintype "passive"))
    )
    (net (code "22") (name "/I2C1_SCL") (class "Default")
      (node (ref "IC4") (pin "42") (pinfunction "TIM4_CH1/PB6_42") (pintype "bidirectional"))
      (node (ref "IC7") (pin "8") (pinfunction "SCL_8") (pintype "passive"))
      (node (ref "JP2") (pin "4") (pinfunction "4_4") (pintype "passive"))
      (node (ref "R12") (pin "2") (pinfunction "2_2") (pintype "passive"))
    )
    (net (code "23") (name "/I2C1_SDA") (class "Default")
      (node (ref "IC4") (pin "43") (pinfunction "TIM4_CH2/PB7_43") (pintype "bidirectional"))
      (node (ref "IC7") (pin "7") (pinfunction "SDA_7") (pintype "passive"))
      (node (ref "JP2") (pin "3") (pinfunction "3_3") (pintype "passive"))
      (node (ref "R13") (pin "2") (pinfunction "2_2") (pintype "passive"))
    )
    (net (code "24") (name "/I2C2_SCL") (class "Default")
      (node (ref "IC2") (pin "23") (pinfunction "SCL_23") (pintype "passive"))
      (node (ref "IC4") (pin "21") (pinfunction "I2C2_SCL/PB10_21") (pintype "bidirectional"))
      (node (ref "IC6") (pin "4") (pinfunction "SCK_4") (pintype "passive"))
      (node (ref "R15") (pin "2") (pinfunction "2_2") (pintype "passive"))
    )
    (net (code "25") (name "/I2C2_SDA") (class "Default")
      (node (ref "IC2") (pin "24") (pinfunction "SDA_24") (pintype "passive"))
      (node (ref "IC4") (pin "22") (pinfunction "I2C2_SDA/PB11_22") (pintype "bidirectional"))
      (node (ref "IC6") (pin "3") (pinfunction "SDI_3") (pintype "passive"))
      (node (ref "R16") (pin "2") (pinfunction "2_2") (pintype "passive"))
    )
    (net (code "26") (name "/I2C_SCL") (class "Default")
      (node (ref "JP1") (pin "3") (pinfunction "3_3") (pintype "passive"))
      (node (ref "Q5") (pin "3") (pinfunction "D_3") (pintype "passive"))
    )
    (net (code "27") (name "/I2C_SDA") (class "Default")
      (node (ref "JP1") (pin "4") (pinfunction "4_4") (pintype "passive"))
      (node (ref "Q6") (pin "3") (pinfunction "D_3") (pintype "passive"))
    )
    (net (code "28") (name "/IO0") (class "Default")
      (node (ref "IC5") (pin "11") (pinfunction "IO0_11") (pintype "passive"))
      (node (ref "Q4") (pin "3") (pinfunction "C_3") (pintype "passive"))
    )
    (net (code "29") (name "/KEY1") (class "Default")
      (node (ref "C12") (pin "1") (pinfunction "1_1") (pintype "passive"))
      (node (ref "IC4") (pin "27") (pinfunction "SPI2_MISO/PB14_27") (pintype "bidirectional"))
      (node (ref "K1") (pin "c") (pinfunction "c_c") (pintype "passive"))
      (node (ref "K1") (pin "d") (pinfunction "d_d") (pintype "passive"))
      (node (ref "R20") (pin "1") (pinfunction "1_1") (pintype "passive"))
    )
    (net (code "30") (name "/KEY2") (class "Default")
      (node (ref "C13") (pin "1") (pinfunction "1_1") (pintype "passive"))
      (node (ref "IC4") (pin "26") (pinfunction "SPI2_SCK/PB13_26") (pintype "bidirectional"))
      (node (ref "K1") (pin "f") (pinfunction "f_f") (pintype "passive"))
      (node (ref "K1") (pin "g") (pinfunction "g_g") (pintype "passive"))
      (node (ref "R21") (pin "1") (pinfunction "1_1") (pintype "passive"))
    )
    (net (code "31") (name "/KEY3") (class "Default")
      (node (ref "C17") (pin "1") (pinfunction "1_1") (pintype "passive"))
      (node (ref "IC4") (pin "25") (pinfunction "SPI2_NSS/PB12_25") (pintype "bidirectional"))
      (node (ref "K1") (pin "e") (pinfunction "e_e") (pintype "passive"))
      (node (ref "R22") (pin "1") (pinfunction "1_1") (pintype "passive"))
    )
    (net (code "32") (name "/KEY4") (class "Default")
      (node (ref "DZx1") (pin "2") (pinfunction "2_2") (pintype "passive"))
      (node (ref "IC4") (pin "28") (pinfunction "SPI2_MOSI/PB15_28") (pintype "bidirectional"))
      (node (ref "R1") (pin "2") (pinfunction "2_2") (pintype "passive"))
    )
    (net (code "33") (name "/LED") (class "Default")
      (node (ref "IC4") (pin "19") (pinfunction "TIM3_CH4/PB1_19") (pintype "bidirectional"))
      (node (ref "LED1") (pin "2") (pinfunction "K_2") (pintype "passive"))
    )
    (net (code "34") (name "/MAX_INT") (class "Default")
      (node (ref "IC1") (pin "13") (pinfunction "~{INT}_13") (pintype "open_collector"))
      (node (ref "IC4") (pin "33") (pinfunction "PA12/USBDP_33") (pintype "bidirectional"))
      (node (ref "JP1") (pin "5") (pinfunction "5_5") (pintype "passive"))
      (node (ref "JP2") (pin "2") (pinfunction "2_2") (pintype "passive"))
      (node (ref "R25") (pin "1") (pinfunction "1_1") (pintype "passive"))
    )
    (net (code "35") (name "/MAX_SCL") (class "Default")
      (node (ref "IC1") (pin "2") (pinfunction "SCL_2") (pintype "bidirectional"))
      (node (ref "Q5") (pin "2") (pinfunction "S_2") (pintype "passive"))
      (node (ref "R18") (pin "2") (pinfunction "2_2") (pintype "passive"))
    )
    (net (code "36") (name "/MAX_SDA") (class "Default")
      (node (ref "IC1") (pin "3") (pinfunction "SDA_3") (pintype "bidirectional"))
      (node (ref "Q6") (pin "2") (pinfunction "S_2") (pintype "passive"))
      (node (ref "R19") (pin "2") (pinfunction "2_2") (pintype "passive"))
    )
    (net (code "37") (name "/MPU_INT") (class "Default")
      (node (ref "IC2") (pin "12") (pinfunction "INT_12") (pintype "passive"))
      (node (ref "IC4") (pin "32") (pinfunction "PA11/USBDM_32") (pintype "bidirectional"))
    )
    (net (code "38") (name "/NRST") (class "Default")
      (node (ref "C32") (pin "2") (pinfunction "2_2") (pintype "passive"))
      (node (ref "IC4") (pin "7") (pinfunction "NRST_7") (pintype "bidirectional"))
      (node (ref "R37") (pin "1") (pinfunction "1_1") (pintype "passive"))
      (node (ref "R41") (pin "1") (pinfunction "1_1") (pintype "passive"))
      (node (ref "SW_RST2") (pin "1") (pinfunction "1_1") (pintype "passive"))
    )
    (net (code "39") (name "/OLED_EN") (class "Default")
      (node (ref "JP3") (pin "4") (pinfunction "GPIO_4") (pintype "passive"))
      (node (ref "R32") (pin "2") (pinfunction "2_2") (pintype "passive"))
    )
    (net (code "40") (name "/OLED_RES") (class "Default")
      (node (ref "C39") (pin "2") (pinfunction "2_2") (pintype "passive"))
      (node (ref "IC4") (pin "29") (pinfunction "PA8/TIM1_CH1_29") (pintype "bidirectional"))
      (node (ref "IC5") (pin "13") (pinfunction "IO5_13") (pintype "passive"))
      (node (ref "JP3") (pin "12") (pinfunction "RES#_12") (pintype "passive"))
      (node (ref "R40") (pin "2") (pinfunction "2_2") (pintype "passive"))
    )
    (net (code "41") (name "/OSC_IN") (class "Default")
      (node (ref "C31") (pin "1") (pinfunction "1_1") (pintype "passive"))
      (node (ref "IC4") (pin "5") (pinfunction "OSC_IN/PD0_5") (pintype "input"))
      (node (ref "X1") (pin "1") (pinfunction "1_1") (pintype "passive"))
    )
    (net (code "42") (name "/OSC_OUT") (class "Default")
      (node (ref "C33") (pin "1") (pinfunction "1_1") (pintype "passive"))
      (node (ref "IC4") (pin "6") (pinfunction "OSC_OUT/PD1_6") (pintype "output"))
      (node (ref "X1") (pin "3") (pinfunction "3_3") (pintype "passive"))
    )
    (net (code "43") (name "/POWER_EN") (class "Default")
      (node (ref "IC4") (pin "38") (pinfunction "PA15/JTDI_38") (pintype "bidirectional"))
      (node (ref "R8") (pin "2") (pinfunction "2_2") (pintype "passive"))
    )
    (net (code "44") (name "/RTS0") (class "Default")
      (node (ref "IC8") (pin "19") (pinfunction "RTS0_19") (pintype "passive"))
      (node (ref "Q8") (pin "2") (pinfunction "E_2") (pintype "passive"))
      (node (ref "R47") (pin "2") (pinfunction "2_2") (pintype "passive"))
    )
    (net (code "45") (name "/RTS1") (class "Default")
      (node (ref "IC8") (pin "11") (pinfunction "RTS1_11") (pintype "passive"))
      (node (ref "Q3") (pin "2") (pinfunction "E_2") (pintype "passive"))
      (node (ref "R23") (pin "2") (pinfunction "2_2") (pintype "passive"))
    )
    (net (code "46") (name "/STDBY") (class "Default")
      (node (ref "IC10") (pin "7") (pinfunction "CHRG#_7") (pintype "passive"))
      (node (ref "IC4") (pin "46") (pinfunction "TIM4_CH4/PB9_46") (pintype "bidirectional"))
      (node (ref "R30") (pin "1") (pinfunction "1_1") (pintype "passive"))
    )
    (net (code "47") (name "/SWCLK") (class "Default")
      (node (ref "IC4") (pin "37") (pinfunction "PA14/JTCK/SWCLK_37") (pintype "bidirectional"))
      (node (ref "JP4") (pin "2") (pinfunction "2_2") (pintype "passive"))
    )
    (net (code "48") (name "/SWDIO") (class "Default")
      (node (ref "IC4") (pin "34") (pinfunction "PA13/JTMS/SWDIO_34") (pintype "bidirectional"))
      (node (ref "JP4") (pin "3") (pinfunction "3_3") (pintype "passive"))
    )
    (net (code "49") (name "/USART1_RX") (class "Default")
      (node (ref "IC4") (pin "31") (pinfunction "PA10/USART1_RX_31") (pintype "bidirectional"))
      (node (ref "IC8") (pin "21") (pinfunction "TXD0_21") (pintype "passive"))
    )
    (net (code "50") (name "/USART1_TX") (class "Default")
      (node (ref "IC4") (pin "30") (pinfunction "PA9/USART1_TX_30") (pintype "bidirectional"))
      (node (ref "IC8") (pin "20") (pinfunction "RXD0_20") (pintype "passive"))
    )
    (net (code "51") (name "/USBC_N") (class "Default")
      (node (ref "IC8") (pin "4") (pinfunction "UD-_4") (pintype "passive"))
      (node (ref "USB1") (pin "A7") (pinfunction "DN1_A7") (pintype "passive"))
      (node (ref "USB1") (pin "B7") (pinfunction "DN2_B7") (pintype "passive"))
    )
    (net (code "52") (name "/USBC_P") (class "Default")
      (node (ref "IC8") (pin "3") (pinfunction "UD+_3") (pintype "passive"))
      (node (ref "USB1") (pin "A6") (pinfunction "DP1_A6") (pintype "passive"))
      (node (ref "USB1") (pin "B6") (pinfunction "DP2_B6") (pintype "passive"))
    )
    (net (code "53") (name "BAT+") (class "Default")
      (node (ref "C28") (pin "1") (pinfunction "1_1") (pintype "passive"))
      (node (ref "H1") (pin "+") (pinfunction "+_+") (pintype "passive"))
      (node (ref "IC10") (pin "5") (pinfunction "BAT_5") (pintype "passive"))
      (node (ref "IC7") (pin "6") (pinfunction "VBAT_6") (pintype "passive"))
      (node (ref "Q1") (pin "2") (pinfunction "S_2") (pintype "passive"))
      (node (ref "R3") (pin "2") (pinfunction "2_2") (pintype "passive"))
      (node (ref "R5") (pin "1") (pinfunction "1_1") (pintype "passive"))
    )
    (net (code "54") (name "BAT-") (class "Default")
      (node (ref "C5") (pin "1") (pinfunction "1_1") (pintype "passive"))
      (node (ref "H1") (pin "-") (pinfunction "-_-") (pintype "passive"))
      (node (ref "IC3") (pin "1") (pinfunction "OVD_1") (pintype "passive"))
      (node (ref "IC3") (pin "5") (pinfunction "IS1_5") (pintype "passive"))
      (node (ref "IC3") (pin "6") (pinfunction "VSS_6") (pintype "passive"))
      (node (ref "R7") (pin "1") (pinfunction "1_1") (pintype "passive"))
    )
    (net (code "55") (name "GND") (class "Default")
      (node (ref "C1") (pin "2") (pinfunction "2_2") (pintype "passive"))
      (node (ref "C10") (pin "1") (pinfunction "1_1") (pintype "passive"))
      (node (ref "C11") (pin "1") (pinfunction "1_1") (pintype "passive"))
      (node (ref "C12") (pin "2") (pinfunction "2_2") (pintype "passive"))
      (node (ref "C13") (pin "2") (pinfunction "2_2") (pintype "passive"))
      (node (ref "C14") (pin "2") (pinfunction "2_2") (pintype "passive"))
      (node (ref "C15") (pin "2") (pinfunction "2_2") (pintype "passive"))
      (node (ref "C16") (pin "2") (pinfunction "2_2") (pintype "passive"))
      (node (ref "C17") (pin "2") (pinfunction "2_2") (pintype "passive"))
      (node (ref "C18") (pin "1") (pinfunction "1_1") (pintype "passive"))
      (node (ref "C19") (pin "1") (pinfunction "1_1") (pintype "passive"))
      (node (ref "C2") (pin "1") (pinfunction "1_1") (pintype "passive"))
      (node (ref "C20") (pin "1") (pinfunction "1_1") (pintype "passive"))
      (node (ref "C21") (pin "1") (pinfunction "1_1") (pintype "passive"))
      (node (ref "C22") (pin "1") (pinfunction "1_1") (pintype "passive"))
      (node (ref "C24") (pin "1") (pinfunction "1_1") (pintype "passive"))
      (node (ref "C25") (pin "1") (pinfunction "1_1") (pintype "passive"))
      (node (ref "C26") (pin "1") (pinfunction "1_1") (pintype "passive"))
      (node (ref "C27") (pin "1") (pinfunction "1_1") (pintype "passive"))
      (node (ref "C28") (pin "2") (pinfunction "2_2") (pintype "passive"))
      (node (ref "C29") (pin "2") (pinfunction "2_2") (pintype "passive"))
      (node (ref "C3") (pin "2") (pinfunction "2_2") (pintype "passive"))
      (node (ref "C30") (pin "2") (pinfunction "2_2") (pintype "passive"))
      (node (ref "C31") (pin "2") (pinfunction "2_2") (pintype "passive"))
      (node (ref "C32") (pin "1") (pinfunction "1_1") (pintype "passive"))
      (node (ref "C33") (pin "2") (pinfunction "2_2") (pintype "passive"))
      (node (ref "C34") (pin "2") (pinfunction "2_2") (pintype "passive"))
      (node (ref "C35") (pin "2") (pinfunction "2_2") (pintype "passive"))
      (node (ref "C36") (pin "2") (pinfunction "2_2") (pintype "passive"))
      (node (ref "C37") (pin "2") (pinfunction "2_2") (pintype "passive"))
      (node (ref "C38") (pin "2") (pinfunction "2_2") (pintype "passive"))
      (node (ref "C39") (pin "1") (pinfunction "1_1") (pintype "passive"))
      (node (ref "C4") (pin "1") (pinfunction "1_1") (pintype "passive"))
      (node (ref "C41") (pin "1") (pinfunction "1_1") (pintype "passive"))
      (node (ref "C42") (pin "2") (pinfunction "2_2") (pintype "passive"))
      (node (ref "C43") (pin "1") (pinfunction "1_1") (pintype "passive"))
      (node (ref "C44") (pin "2") (pinfunction "2_2") (pintype "passive"))
      (node (ref "C6") (pin "2") (pinfunction "2_2") (pintype "passive"))
      (node (ref "C7") (pin "2") (pinfunction "K_2") (pintype "passive"))
      (node (ref "C8") (pin "1") (pinfunction "1_1") (pintype "passive"))
      (node (ref "C9") (pin "2") (pinfunction "2_2") (pintype "passive"))
      (node (ref "E1") (pin "2") (pinfunction "K_2") (pintype "passive"))
      (node (ref "E2") (pin "2") (pinfunction "K_2") (pintype "passive"))
      (node (ref "IC1") (pin "4") (pinfunction "PGND_4") (pintype "power_in"))
      (node (ref "IC10") (pin "1") (pinfunction "TEMP_1") (pintype "passive"))
      (node (ref "IC10") (pin "3") (pinfunction "GND_3") (pintype "passive"))
      (node (ref "IC11") (pin "2") (pinfunction "GND_2") (pintype "passive"))
      (node (ref "IC12") (pin "2") (pinfunction "GND_2") (pintype "passive"))
      (node (ref "IC13") (pin "1") (pinfunction "GND_1") (pintype "passive"))
      (node (ref "IC14") (pin "3") (pinfunction "GND_3") (pintype "passive"))
      (node (ref "IC15") (pin "4") (pinfunction "GND_4") (pintype "passive"))
      (node (ref "IC2") (pin "18") (pinfunction "GND_18") (pintype "passive"))
      (node (ref "IC3") (pin "4") (pinfunction "IS2_4") (pintype "passive"))
      (node (ref "IC4") (pin "23") (pinfunction "VSS_1_23") (pintype "power_in"))
      (node (ref "IC4") (pin "35") (pinfunction "VSS_2_35") (pintype "power_in"))
      (node (ref "IC4") (pin "47") (pinfunction "VSS_3_47") (pintype "power_in"))
      (node (ref "IC4") (pin "8") (pinfunction "VSSA_8") (pintype "power_in"))
      (node (ref "IC5") (pin "18") (pinfunction "GND_18") (pintype "passive"))
      (node (ref "IC5") (pin "19") (pinfunction "GND_19") (pintype "passive"))
      (node (ref "IC5") (pin "2") (pinfunction "GND_2") (pintype "passive"))
      (node (ref "IC6") (pin "1") (pinfunction "GND_1") (pintype "passive"))
      (node (ref "IC6") (pin "7") (pinfunction "GND_7") (pintype "passive"))
      (node (ref "IC7") (pin "5") (pinfunction "GND_5") (pintype "passive"))
      (node (ref "IC8") (pin "2") (pinfunction "GND_2") (pintype "passive"))
      (node (ref "IC8") (pin "25") (pinfunction "EP_25") (pintype "passive"))
      (node (ref "IC9") (pin "2") (pinfunction "GND_2") (pintype "passive"))
      (node (ref "JP1") (pin "6") (pinfunction "6_6") (pintype "passive"))
      (node (ref "JP2") (pin "1") (pinfunction "1_1") (pintype "passive"))
      (node (ref "JP3") (pin "1") (pinfunction "VSS_1") (pintype "passive"))
      (node (ref "JP3") (pin "14") (pinfunction "WR_14") (pintype "passive"))
      (node (ref "JP3") (pin "15") (pinfunction "RD_15") (pintype "passive"))
      (node (ref "JP3") (pin "19") (pinfunction "D3_19") (pintype "passive"))
      (node (ref "JP3") (pin "20") (pinfunction "D4_20") (pintype "passive"))
      (node (ref "JP3") (pin "21") (pinfunction "D5_21") (pintype "passive"))
      (node (ref "JP3") (pin "22") (pinfunction "D6_22") (pintype "passive"))
      (node (ref "JP3") (pin "23") (pinfunction "D7_23") (pintype "passive"))
      (node (ref "JP3") (pin "25") (pinfunction "VSS_25") (pintype "passive"))
      (node (ref "JP3") (pin "7") (pinfunction "BS1_7") (pintype "passive"))
      (node (ref "JP3") (pin "8") (pinfunction "BS2_8") (pintype "passive"))
      (node (ref "JP3") (pin "9") (pinfunction "VSS_9") (pintype "passive"))
      (node (ref "JP4") (pin "1") (pinfunction "1_1") (pintype "passive"))
      (node (ref "K1") (pin "a") (pinfunction "a_a") (pintype "passive"))
      (node (ref "Q2") (pin "2") (pinfunction "E_2") (pintype "passive"))
      (node (ref "Q7") (pin "2") (pinfunction "E_2") (pintype "passive"))
      (node (ref "R24") (pin "1") (pinfunction "1_1") (pintype "passive"))
      (node (ref "R33") (pin "1") (pinfunction "1_1") (pintype "passive"))
      (node (ref "R34") (pin "1") (pinfunction "1_1") (pintype "passive"))
      (node (ref "R35") (pin "1") (pinfunction "1_1") (pintype "passive"))
      (node (ref "R36") (pin "1") (pinfunction "1_1") (pintype "passive"))
      (node (ref "R38") (pin "2") (pinfunction "2_2") (pintype "passive"))
      (node (ref "R39") (pin "2") (pinfunction "2_2") (pintype "passive"))
      (node (ref "R4") (pin "2") (pinfunction "2_2") (pintype "passive"))
      (node (ref "R46") (pin "1") (pinfunction "1_1") (pintype "passive"))
      (node (ref "R6") (pin "1") (pinfunction "1_1") (pintype "passive"))
      (node (ref "R7") (pin "2") (pinfunction "2_2") (pintype "passive"))
      (node (ref "R9") (pin "1") (pinfunction "1_1") (pintype "passive"))
      (node (ref "SW_PWR") (pin "2") (pinfunction "2_2") (pintype "passive"))
      (node (ref "SW_RST1") (pin "2") (pinfunction "2_2") (pintype "passive"))
      (node (ref "SW_RST2") (pin "2") (pinfunction "2_2") (pintype "passive"))
      (node (ref "USB1") (pin "A1B12") (pinfunction "GND_A1B12") (pintype "passive"))
      (node (ref "USB1") (pin "B1A12") (pinfunction "GND_B1A12") (pintype "passive"))
      (node (ref "X1") (pin "2") (pinfunction "2_2") (pintype "passive"))
      (node (ref "X1") (pin "4") (pinfunction "4_4") (pintype "passive"))
    )
    (net (code "56") (name "Net-(BUZZER1--)") (class "Default")
      (node (ref "BUZZER1") (pin "2") (pinfunction "-_2") (pintype "passive"))
      (node (ref "Q7") (pin "3") (pinfunction "C_3") (pintype "passive"))
    )
    (net (code "57") (name "Net-(C2-Pad2)") (class "Default")
      (node (ref "C2") (pin "2") (pinfunction "2_2") (pintype "passive"))
      (node (ref "DZx1") (pin "3") (pinfunction "3_3") (pintype "passive"))
      (node (ref "SW_PWR") (pin "1") (pinfunction "1_1") (pintype "passive"))
    )
    (net (code "58") (name "Net-(D1-A)") (class "Default")
      (node (ref "D1") (pin "1") (pinfunction "A_1") (pintype "passive"))
      (node (ref "IC9") (pin "1") (pinfunction "SW_1") (pintype "passive"))
      (node (ref "L1") (pin "2") (pinfunction "2_2") (pintype "passive"))
    )
    (net (code "59") (name "Net-(D2-A)") (class "Default")
      (node (ref "C44") (pin "1") (pinfunction "1_1") (pintype "passive"))
      (node (ref "D2") (pin "1") (pinfunction "A_1") (pintype "passive"))
      (node (ref "IC14") (pin "4") (pinfunction "E_4") (pintype "passive"))
      (node (ref "R49") (pin "1") (pinfunction "1_1") (pintype "passive"))
    )
    (net (code "60") (name "Net-(E2-A)") (class "Default")
      (node (ref "E2") (pin "1") (pinfunction "A_1") (pintype "passive"))
      (node (ref "JP3") (pin "3") (pinfunction "VCOMH_3") (pintype "passive"))
    )
    (net (code "61") (name "Net-(IC1-GND)") (class "Default")
      (node (ref "IC1") (pin "12") (pinfunction "GND_12") (pintype "power_in"))
      (node (ref "R6") (pin "2") (pinfunction "2_2") (pintype "passive"))
    )
    (net (code "62") (name "Net-(IC2-AD0)") (class "Default")
      (node (ref "IC2") (pin "9") (pinfunction "AD0_9") (pintype "passive"))
      (node (ref "R4") (pin "1") (pinfunction "1_1") (pintype "passive"))
    )
    (net (code "63") (name "Net-(IC2-CPOUT)") (class "Default")
      (node (ref "C8") (pin "2") (pinfunction "2_2") (pintype "passive"))
      (node (ref "IC2") (pin "20") (pinfunction "CPOUT_20") (pintype "passive"))
    )
    (net (code "64") (name "Net-(IC2-REGOUT)") (class "Default")
      (node (ref "C9") (pin "1") (pinfunction "1_1") (pintype "passive"))
      (node (ref "IC2") (pin "10") (pinfunction "REGOUT_10") (pintype "passive"))
    )
    (net (code "65") (name "Net-(IC2-VLOGIC)") (class "Default")
      (node (ref "C3") (pin "1") (pinfunction "1_1") (pintype "passive"))
      (node (ref "IC2") (pin "8") (pinfunction "VLOGIC_8") (pintype "passive"))
    )
    (net (code "66") (name "Net-(IC3-VDD)") (class "Default")
      (node (ref "C5") (pin "2") (pinfunction "2_2") (pintype "passive"))
      (node (ref "IC3") (pin "8") (pinfunction "VDD_8") (pintype "passive"))
      (node (ref "R3") (pin "1") (pinfunction "1_1") (pintype "passive"))
    )
    (net (code "67") (name "Net-(IC6-CSB)") (class "Default")
      (node (ref "IC6") (pin "2") (pinfunction "CSB_2") (pintype "passive"))
      (node (ref "R17") (pin "1") (pinfunction "1_1") (pintype "passive"))
    )
    (net (code "68") (name "Net-(IC6-SDO)") (class "Default")
      (node (ref "IC6") (pin "5") (pinfunction "SDO_5") (pintype "passive"))
      (node (ref "R24") (pin "2") (pinfunction "2_2") (pintype "passive"))
    )
    (net (code "69") (name "Net-(IC7-32KHz)") (class "Default")
      (node (ref "IC7") (pin "1") (pinfunction "32KHz_1") (pintype "passive"))
      (node (ref "R11") (pin "2") (pinfunction "2_2") (pintype "passive"))
    )
    (net (code "70") (name "Net-(IC8-V3)") (class "Default")
      (node (ref "C30") (pin "1") (pinfunction "1_1") (pintype "passive"))
      (node (ref "IC8") (pin "6") (pinfunction "V3_6") (pintype "passive"))
    )
    (net (code "71") (name "Net-(IC9-FB)") (class "Default")
      (node (ref "C23") (pin "1") (pinfunction "1_1") (pintype "passive"))
      (node (ref "IC9") (pin "3") (pinfunction "FB_3") (pintype "passive"))
      (node (ref "R28") (pin "1") (pinfunction "1_1") (pintype "passive"))
      (node (ref "R33") (pin "2") (pinfunction "2_2") (pintype "passive"))
    )
    (net (code "72") (name "Net-(IC9-SHDN#)") (class "Default")
      (node (ref "IC9") (pin "4") (pinfunction "SHDN#_4") (pintype "passive"))
      (node (ref "R32") (pin "1") (pinfunction "1_1") (pintype "passive"))
      (node (ref "R34") (pin "2") (pinfunction "2_2") (pintype "passive"))
    )
    (net (code "73") (name "Net-(IC10-CE)") (class "Default")
      (node (ref "IC10") (pin "8") (pinfunction "CE_8") (pintype "passive"))
      (node (ref "R27") (pin "1") (pinfunction "1_1") (pintype "passive"))
    )
    (net (code "74") (name "Net-(IC10-PROG)") (class "Default")
      (node (ref "IC10") (pin "2") (pinfunction "PROG_2") (pintype "passive"))
      (node (ref "R36") (pin "2") (pinfunction "2_2") (pintype "passive"))
    )
    (net (code "75") (name "Net-(IC10-VCC)") (class "Default")
      (node (ref "C27") (pin "2") (pinfunction "2_2") (pintype "passive"))
      (node (ref "IC10") (pin "4") (pinfunction "VCC_4") (pintype "passive"))
      (node (ref "R29") (pin "1") (pinfunction "1_1") (pintype "passive"))
    )
    (net (code "76") (name "Net-(IC11-C+)") (class "Default")
      (node (ref "C40") (pin "1") (pinfunction "1_1") (pintype "passive"))
      (node (ref "IC11") (pin "6") (pinfunction "C+_6") (pintype "passive"))
    )
    (net (code "77") (name "Net-(IC11-C-)") (class "Default")
      (node (ref "C40") (pin "2") (pinfunction "2_2") (pintype "passive"))
      (node (ref "IC11") (pin "4") (pinfunction "C-_4") (pintype "passive"))
    )
    (net (code "78") (name "Net-(IC14-Y)") (class "Default")
      (node (ref "IC14") (pin "1") (pinfunction "Y_1") (pintype "passive"))
      (node (ref "R41") (pin "2") (pinfunction "2_2") (pintype "passive"))
    )
    (net (code "79") (name "Net-(IC14-Z)") (class "Default")
      (node (ref "IC14") (pin "2") (pinfunction "Z_2") (pintype "passive"))
      (node (ref "Q8") (pin "3") (pinfunction "C_3") (pintype "passive"))
      (node (ref "R42") (pin "2") (pinfunction "2_2") (pintype "passive"))
    )
    (net (code "80") (name "Net-(JP3-IREF)") (class "Default")
      (node (ref "JP3") (pin "10") (pinfunction "IREF_10") (pintype "passive"))
      (node (ref "R35") (pin "2") (pinfunction "2_2") (pintype "passive"))
    )
    (net (code "81") (name "Net-(JP3-VDD)") (class "Default")
      (node (ref "C25") (pin "2") (pinfunction "2_2") (pintype "passive"))
      (node (ref "JP3") (pin "6") (pinfunction "VDD_6") (pintype "passive"))
    )
    (net (code "82") (name "Net-(LED1-A)") (class "Default")
      (node (ref "LED1") (pin "1") (pinfunction "A_1") (pintype "passive"))
      (node (ref "R26") (pin "1") (pinfunction "1_1") (pintype "passive"))
    )
    (net (code "83") (name "Net-(Q1-G)") (class "Default")
      (node (ref "DZx1") (pin "1") (pinfunction "1_1") (pintype "passive"))
      (node (ref "Q1") (pin "1") (pinfunction "G_1") (pintype "passive"))
      (node (ref "Q2") (pin "3") (pinfunction "C_3") (pintype "passive"))
      (node (ref "R5") (pin "2") (pinfunction "2_2") (pintype "passive"))
    )
    (net (code "84") (name "Net-(Q2-B)") (class "Default")
      (node (ref "Q2") (pin "1") (pinfunction "B_1") (pintype "passive"))
      (node (ref "R8") (pin "1") (pinfunction "1_1") (pintype "passive"))
      (node (ref "R9") (pin "2") (pinfunction "2_2") (pintype "passive"))
    )
    (net (code "85") (name "Net-(Q3-B)") (class "Default")
      (node (ref "Q3") (pin "1") (pinfunction "B_1") (pintype "passive"))
      (node (ref "R14") (pin "2") (pinfunction "2_2") (pintype "passive"))
    )
    (net (code "86") (name "Net-(Q4-B)") (class "Default")
      (node (ref "Q4") (pin "1") (pinfunction "B_1") (pintype "passive"))
      (node (ref "R23") (pin "1") (pinfunction "1_1") (pintype "passive"))
    )
    (net (code "87") (name "Net-(Q7-B)") (class "Default")
      (node (ref "Q7") (pin "1") (pinfunction "B_1") (pintype "passive"))
      (node (ref "R44") (pin "2") (pinfunction "2_2") (pintype "passive"))
      (node (ref "R46") (pin "2") (pinfunction "2_2") (pintype "passive"))
    )
    (net (code "88") (name "Net-(Q8-B)") (class "Default")
      (node (ref "Q8") (pin "1") (pinfunction "B_1") (pintype "passive"))
      (node (ref "R45") (pin "2") (pinfunction "2_2") (pintype "passive"))
    )
    (net (code "89") (name "Net-(Q9-B)") (class "Default")
      (node (ref "Q9") (pin "1") (pinfunction "B_1") (pintype "passive"))
      (node (ref "R47") (pin "1") (pinfunction "1_1") (pintype "passive"))
    )
    (net (code "90") (name "Net-(Q9-C)") (class "Default")
      (node (ref "Q9") (pin "3") (pinfunction "C_3") (pintype "passive"))
      (node (ref "R48") (pin "2") (pinfunction "2_2") (pintype "passive"))
    )
    (net (code "91") (name "VBAT") (class "Default")
      (node (ref "C26") (pin "2") (pinfunction "2_2") (pintype "passive"))
      (node (ref "C35") (pin "1") (pinfunction "1_1") (pintype "passive"))
      (node (ref "C37") (pin "1") (pinfunction "1_1") (pintype "passive"))
      (node (ref "C41") (pin "2") (pinfunction "2_2") (pintype "passive"))
      (node (ref "IC11") (pin "3") (pinfunction "EN_3") (pintype "passive"))
      (node (ref "IC11") (pin "5") (pinfunction "VIN_5") (pintype "passive"))
      (node (ref "IC12") (pin "1") (pinfunction "VIN_1") (pintype "passive"))
      (node (ref "IC12") (pin "3") (pinfunction "EN_3") (pintype "passive"))
      (node (ref "IC13") (pin "3") (pinfunction "VIN_3") (pintype "passive"))
      (node (ref "IC9") (pin "5") (pinfunction "VIN_5") (pintype "passive"))
      (node (ref "L1") (pin "1") (pinfunction "1_1") (pintype "passive"))
      (node (ref "Q1") (pin "3") (pinfunction "D_3") (pintype "passive"))
      (node (ref "R1") (pin "1") (pinfunction "1_1") (pintype "passive"))
    )
    (net (code "92") (name "VBUS") (class "Default")
      (node (ref "C34") (pin "1") (pinfunction "1_1") (pintype "passive"))
      (node (ref "IC8") (pin "7") (pinfunction "VDD5_7") (pintype "passive"))
      (node (ref "IC8") (pin "8") (pinfunction "VBUS_8") (pintype "passive"))
      (node (ref "R27") (pin "2") (pinfunction "2_2") (pintype "passive"))
      (node (ref "R29") (pin "2") (pinfunction "2_2") (pintype "passive"))
      (node (ref "USB1") (pin "A4B9") (pinfunction "VBUS_A4B9") (pintype "passive"))
      (node (ref "USB1") (pin "B4A9") (pinfunction "VBUS_B4A9") (pintype "passive"))
    )
    (net (code "93") (name "unconnected-(IC1-NC-Pad1)") (class "Default")
      (node (ref "IC1") (pin "1") (pinfunction "NC_1") (pintype "passive"))
    )
    (net (code "94") (name "unconnected-(IC1-NC-Pad5)") (class "Default")
      (node (ref "IC1") (pin "5") (pinfunction "NC_5") (pintype "passive"))
    )
    (net (code "95") (name "unconnected-(IC1-NC-Pad6)") (class "Default")
      (node (ref "IC1") (pin "6") (pinfunction "NC_6") (pintype "passive"))
    )
    (net (code "96") (name "unconnected-(IC1-NC-Pad7)") (class "Default")
      (node (ref "IC1") (pin "7") (pinfunction "NC_7") (pintype "passive"))
    )
    (net (code "97") (name "unconnected-(IC1-NC-Pad8)") (class "Default")
      (node (ref "IC1") (pin "8") (pinfunction "NC_8") (pintype "passive"))
    )
    (net (code "98") (name "unconnected-(IC1-NC-Pad14)") (class "Default")
      (node (ref "IC1") (pin "14") (pinfunction "NC_14") (pintype "passive"))
    )
    (net (code "99") (name "unconnected-(IC2-AUX_CL-Pad7)") (class "Default")
      (node (ref "IC2") (pin "7") (pinfunction "AUX_CL_7") (pintype "passive"))
    )
    (net (code "100") (name "unconnected-(IC2-AUX_DA-Pad6)") (class "Default")
      (node (ref "IC2") (pin "6") (pinfunction "AUX_DA_6") (pintype "passive"))
    )
    (net (code "101") (name "unconnected-(IC2-CLKIN-Pad1)") (class "Default")
      (node (ref "IC2") (pin "1") (pinfunction "CLKIN_1") (pintype "passive"))
    )
    (net (code "102") (name "unconnected-(IC2-CLKOUT-Pad22)") (class "Default")
      (node (ref "IC2") (pin "22") (pinfunction "CLKOUT_22") (pintype "passive"))
    )
    (net (code "103") (name "unconnected-(IC2-FSYNC-Pad11)") (class "Default")
      (node (ref "IC2") (pin "11") (pinfunction "FSYNC_11") (pintype "passive"))
    )
    (net (code "104") (name "unconnected-(IC2-RESV-Pad19)") (class "Default")
      (node (ref "IC2") (pin "19") (pinfunction "RESV_19") (pintype "passive"))
    )
    (net (code "105") (name "unconnected-(IC2-RESV-Pad21)") (class "Default")
      (node (ref "IC2") (pin "21") (pinfunction "RESV_21") (pintype "passive"))
    )
    (net (code "106") (name "unconnected-(IC3-PIO-Pad2)") (class "Default")
      (node (ref "IC3") (pin "2") (pinfunction "PIO_2") (pintype "passive"))
    )
    (net (code "107") (name "unconnected-(IC3-SNS-Pad3)") (class "Default")
      (node (ref "IC3") (pin "3") (pinfunction "SNS_3") (pintype "passive"))
    )
    (net (code "108") (name "unconnected-(IC4-PB4{slash}JNTRST-Pad40)") (class "Default")
      (node (ref "IC4") (pin "40") (pinfunction "PB4/JNTRST_40") (pintype "bidirectional"))
    )
    (net (code "109") (name "unconnected-(IC4-PC13-TAMPER-RTC-Pad2)") (class "Default")
      (node (ref "IC4") (pin "2") (pinfunction "PC13-TAMPER-RTC_2") (pintype "bidirectional"))
    )
    (net (code "110") (name "unconnected-(IC4-PC14-OSC32_IN-Pad3)") (class "Default")
      (node (ref "IC4") (pin "3") (pinfunction "PC14-OSC32_IN_3") (pintype "bidirectional"))
    )
    (net (code "111") (name "unconnected-(IC4-PC15-OSC32_OUT-Pad4)") (class "Default")
      (node (ref "IC4") (pin "4") (pinfunction "PC15-OSC32_OUT_4") (pintype "bidirectional"))
    )
    (net (code "112") (name "unconnected-(IC5-ADC-Pad3)") (class "Default")
      (node (ref "IC5") (pin "3") (pinfunction "ADC_3") (pintype "passive"))
    )
    (net (code "113") (name "unconnected-(IC5-ANT-Pad1)") (class "Default")
      (node (ref "IC5") (pin "1") (pinfunction "ANT_1") (pintype "passive"))
    )
    (net (code "114") (name "unconnected-(IC5-IO2-Pad10)") (class "Default")
      (node (ref "IC5") (pin "10") (pinfunction "IO2_10") (pintype "passive"))
    )
    (net (code "115") (name "unconnected-(IC7-RST#-Pad4)") (class "Default")
      (node (ref "IC7") (pin "4") (pinfunction "RST#_4") (pintype "passive"))
    )
    (net (code "116") (name "unconnected-(IC8-CTS0-Pad18)") (class "Default")
      (node (ref "IC8") (pin "18") (pinfunction "CTS0_18") (pintype "passive"))
    )
    (net (code "117") (name "unconnected-(IC8-CTS1-Pad10)") (class "Default")
      (node (ref "IC8") (pin "10") (pinfunction "CTS1_10") (pintype "passive"))
    )
    (net (code "118") (name "unconnected-(IC8-DCD0-Pad24)") (class "Default")
      (node (ref "IC8") (pin "24") (pinfunction "DCD0_24") (pintype "passive"))
    )
    (net (code "119") (name "unconnected-(IC8-DCD1-Pad16)") (class "Default")
      (node (ref "IC8") (pin "16") (pinfunction "DCD1_16") (pintype "passive"))
    )
    (net (code "120") (name "unconnected-(IC8-DSR0-Pad22)") (class "Default")
      (node (ref "IC8") (pin "22") (pinfunction "DSR0_22") (pintype "passive"))
    )
    (net (code "121") (name "unconnected-(IC8-DSR1-Pad14)") (class "Default")
      (node (ref "IC8") (pin "14") (pinfunction "DSR1_14") (pintype "passive"))
    )
    (net (code "122") (name "unconnected-(IC8-RI0-Pad1)") (class "Default")
      (node (ref "IC8") (pin "1") (pinfunction "RI0_1") (pintype "passive"))
    )
    (net (code "123") (name "unconnected-(IC8-RI1-Pad17)") (class "Default")
      (node (ref "IC8") (pin "17") (pinfunction "RI1_17") (pintype "passive"))
    )
    (net (code "124") (name "unconnected-(IC8-RST-Pad9)") (class "Default")
      (node (ref "IC8") (pin "9") (pinfunction "RST_9") (pintype "passive"))
    )
    (net (code "125") (name "unconnected-(IC12-NC-Pad4)") (class "Default")
      (node (ref "IC12") (pin "4") (pinfunction "NC_4") (pintype "passive"))
    )
    (net (code "126") (name "unconnected-(JP3-D2-Pad18)") (class "Default")
      (node (ref "JP3") (pin "18") (pinfunction "D2_18") (pintype "passive"))
    )
    (net (code "127") (name "unconnected-(USB1-CC1-PadA5)") (class "Default")
      (node (ref "USB1") (pin "A5") (pinfunction "CC1_A5") (pintype "passive"))
    )
    (net (code "128") (name "unconnected-(USB1-CC2-PadB5)") (class "Default")
      (node (ref "USB1") (pin "B5") (pinfunction "CC2_B5") (pintype "passive"))
    )
    (net (code "129") (name "unconnected-(USB1-SBU1-PadA8)") (class "Default")
      (node (ref "USB1") (pin "A8") (pinfunction "SBU1_A8") (pintype "passive"))
    )
    (net (code "130") (name "unconnected-(USB1-SBU2-PadB8)") (class "Default")
      (node (ref "USB1") (pin "B8") (pinfunction "SBU2_B8") (pintype "passive"))
    )
    (net (code "131") (name "unconnected-(USB1-SHELL-Pad1)") (class "Default")
      (node (ref "USB1") (pin "1") (pinfunction "SHELL_1") (pintype "passive"))
    )
    (net (code "132") (name "unconnected-(USB1-SHELL-Pad2)") (class "Default")
      (node (ref "USB1") (pin "2") (pinfunction "SHELL_2") (pintype "passive"))
    )
    (net (code "133") (name "unconnected-(USB1-SHELL-Pad3)") (class "Default")
      (node (ref "USB1") (pin "3") (pinfunction "SHELL_3") (pintype "passive"))
    )
    (net (code "134") (name "unconnected-(USB1-SHELL-Pad4)") (class "Default")
      (node (ref "USB1") (pin "4") (pinfunction "SHELL_4") (pintype "passive"))
    )
  )
)
